# FPGA_board_V2.net
KiCad netlist of a schematic drawn in EAGLE
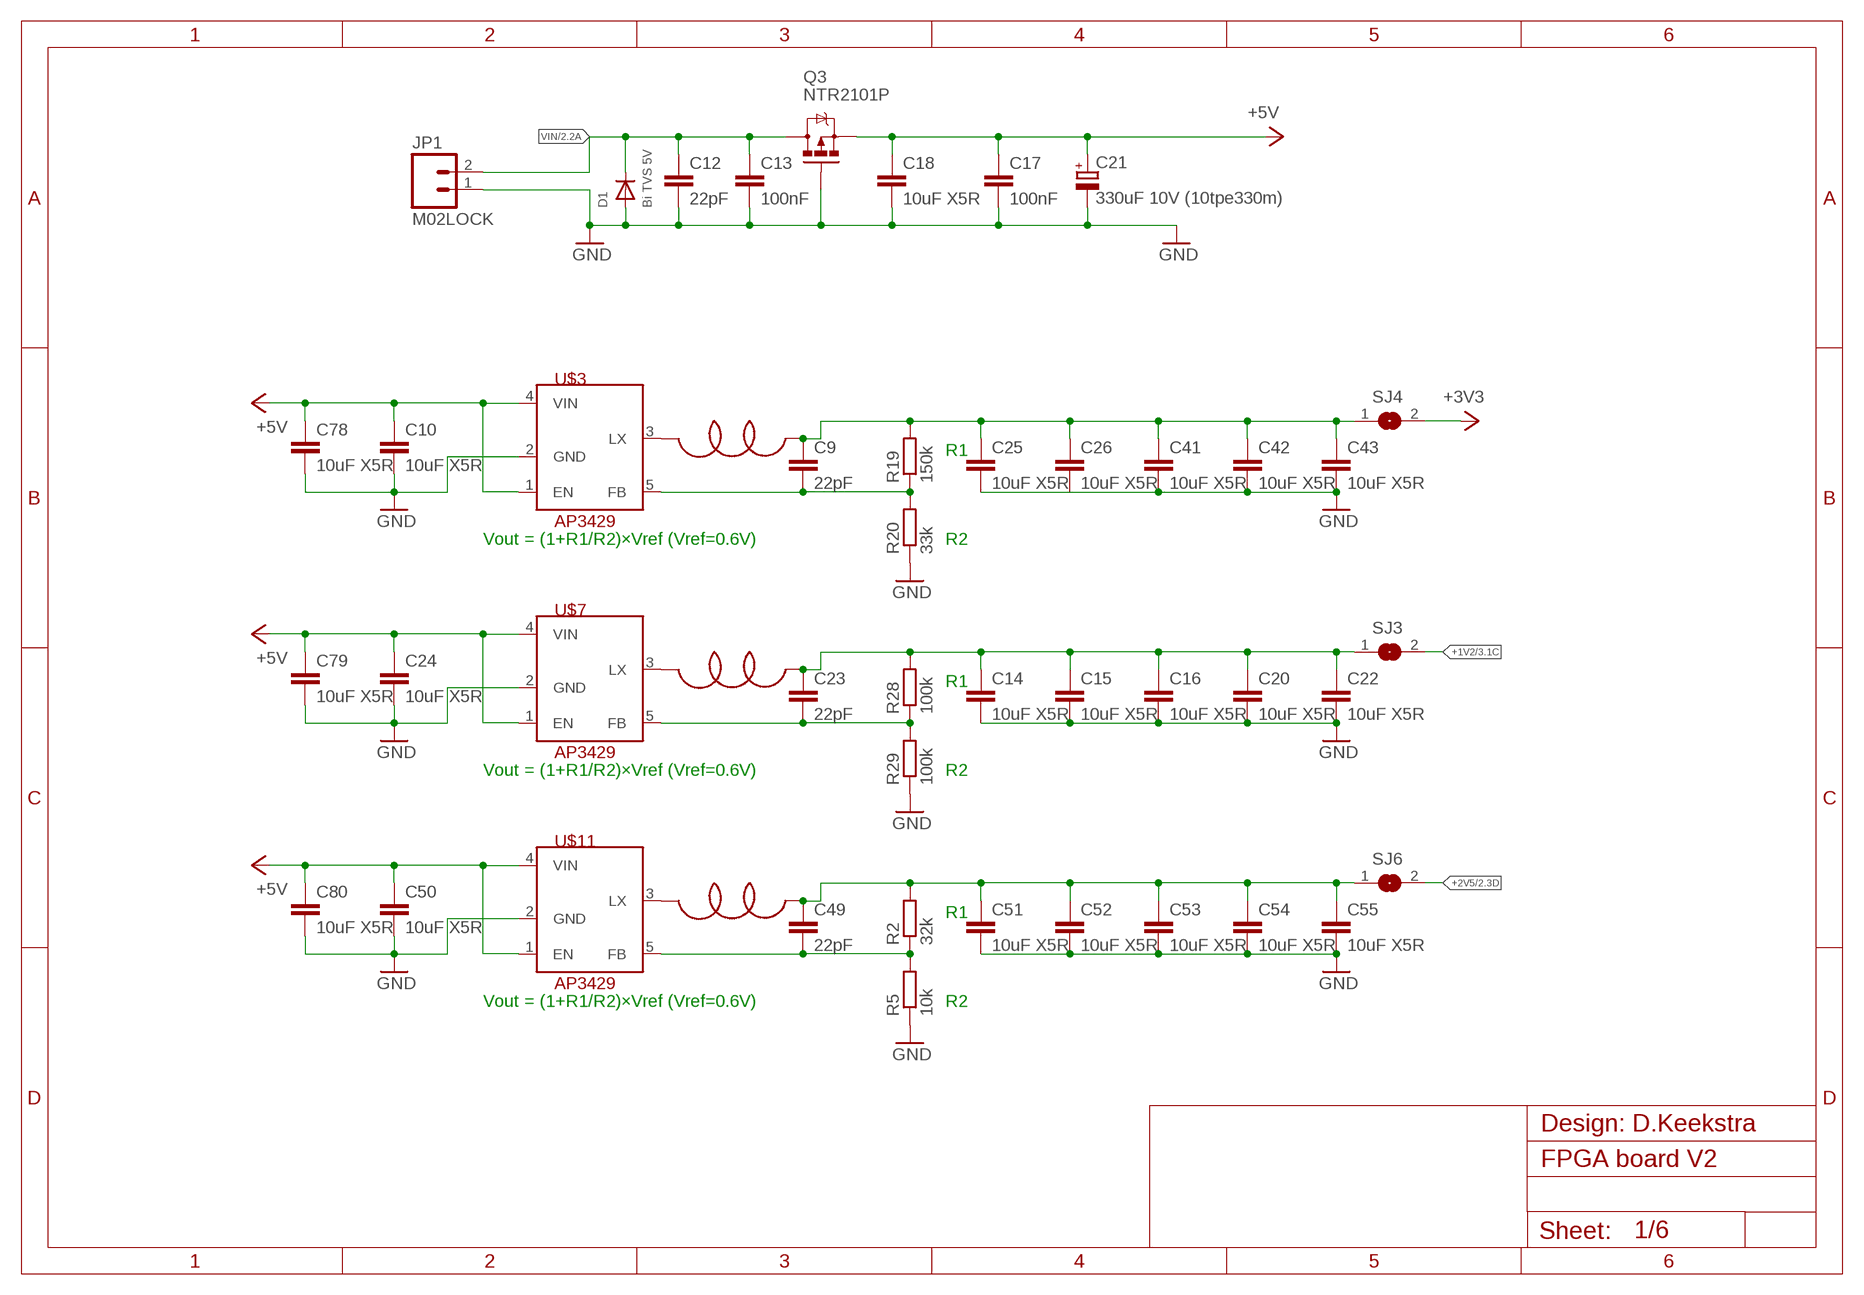
[diagram p0: schematic, sheet 1]
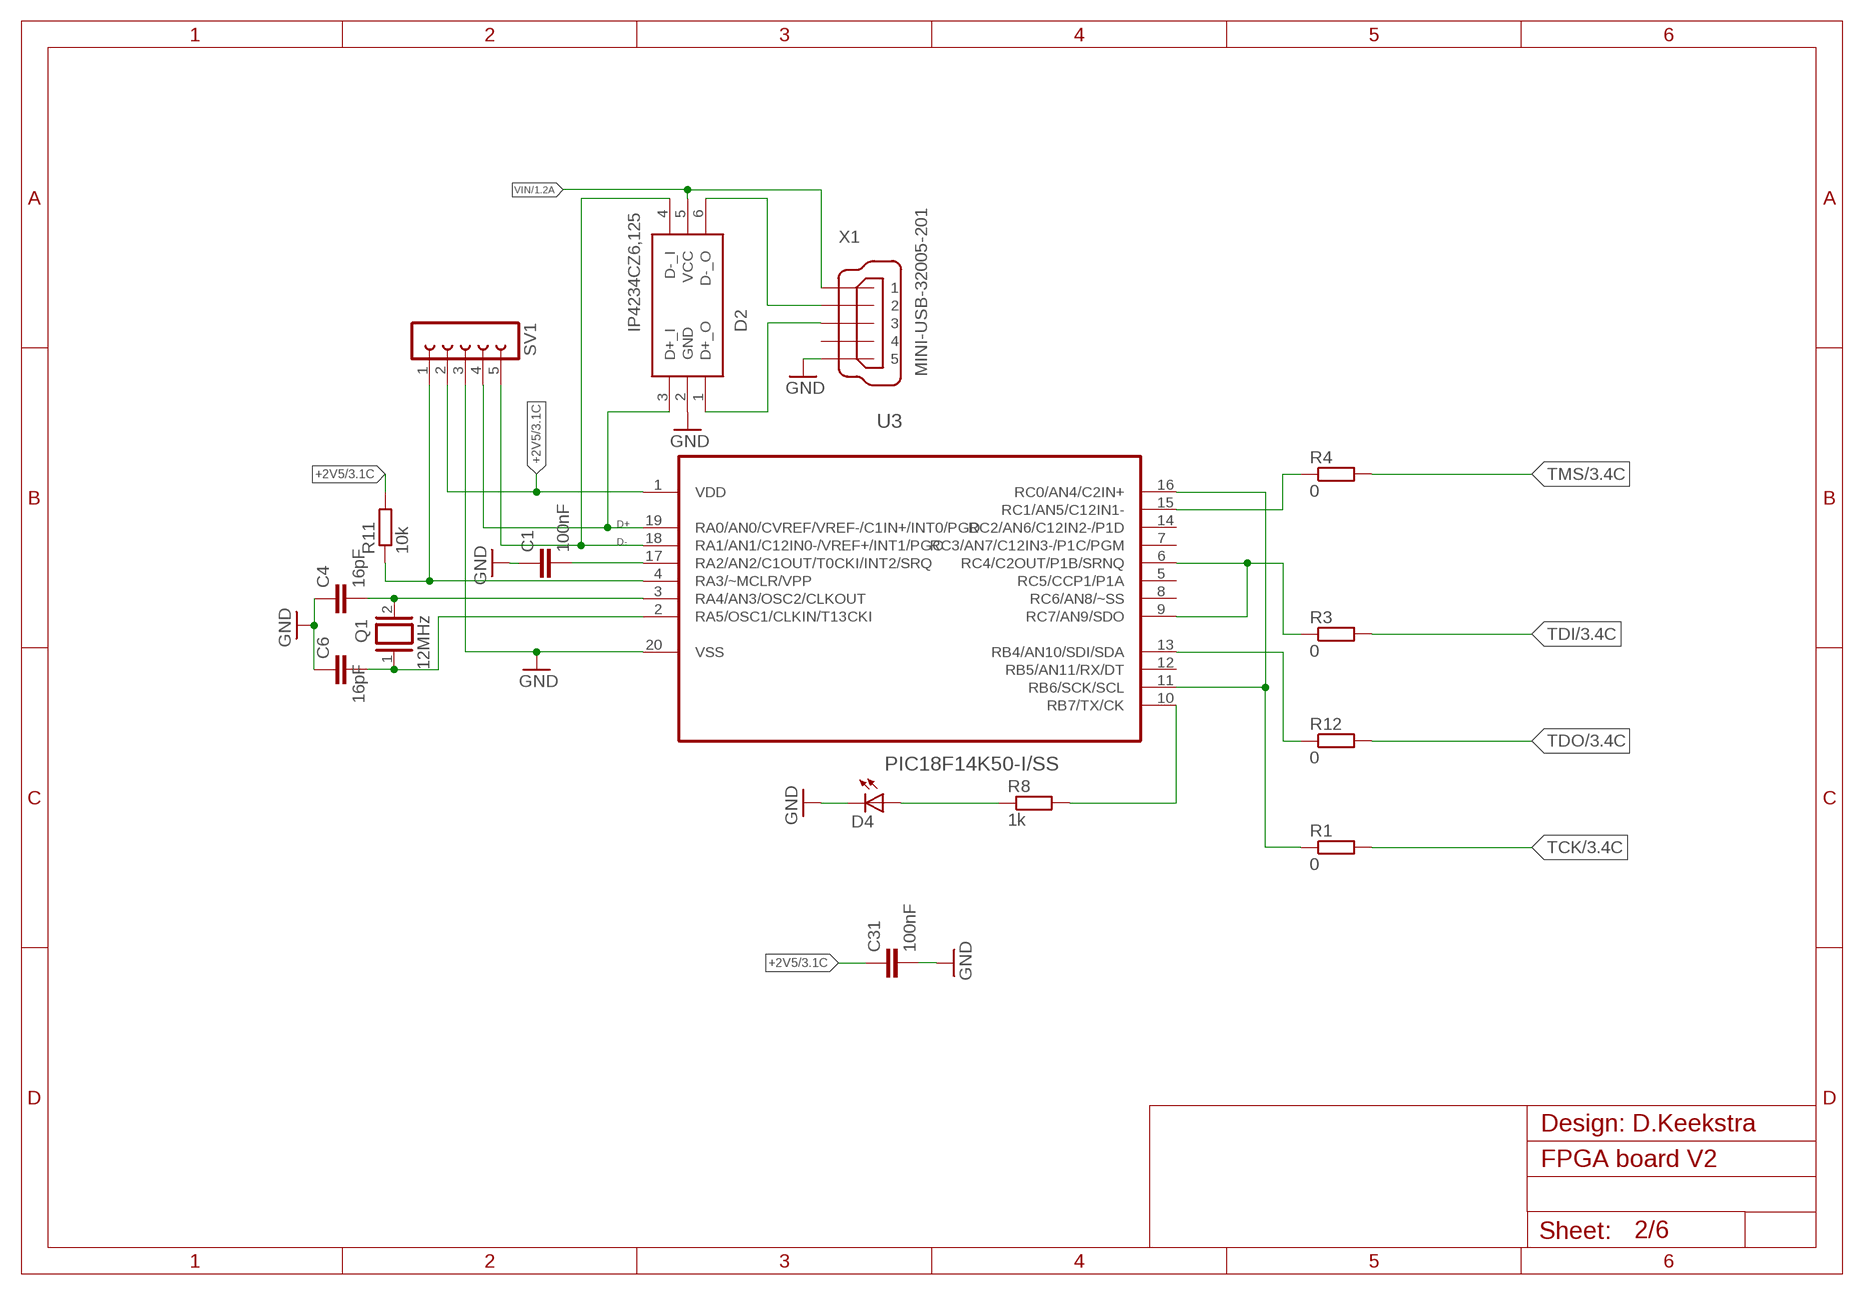
[diagram p1: schematic, sheet 2]
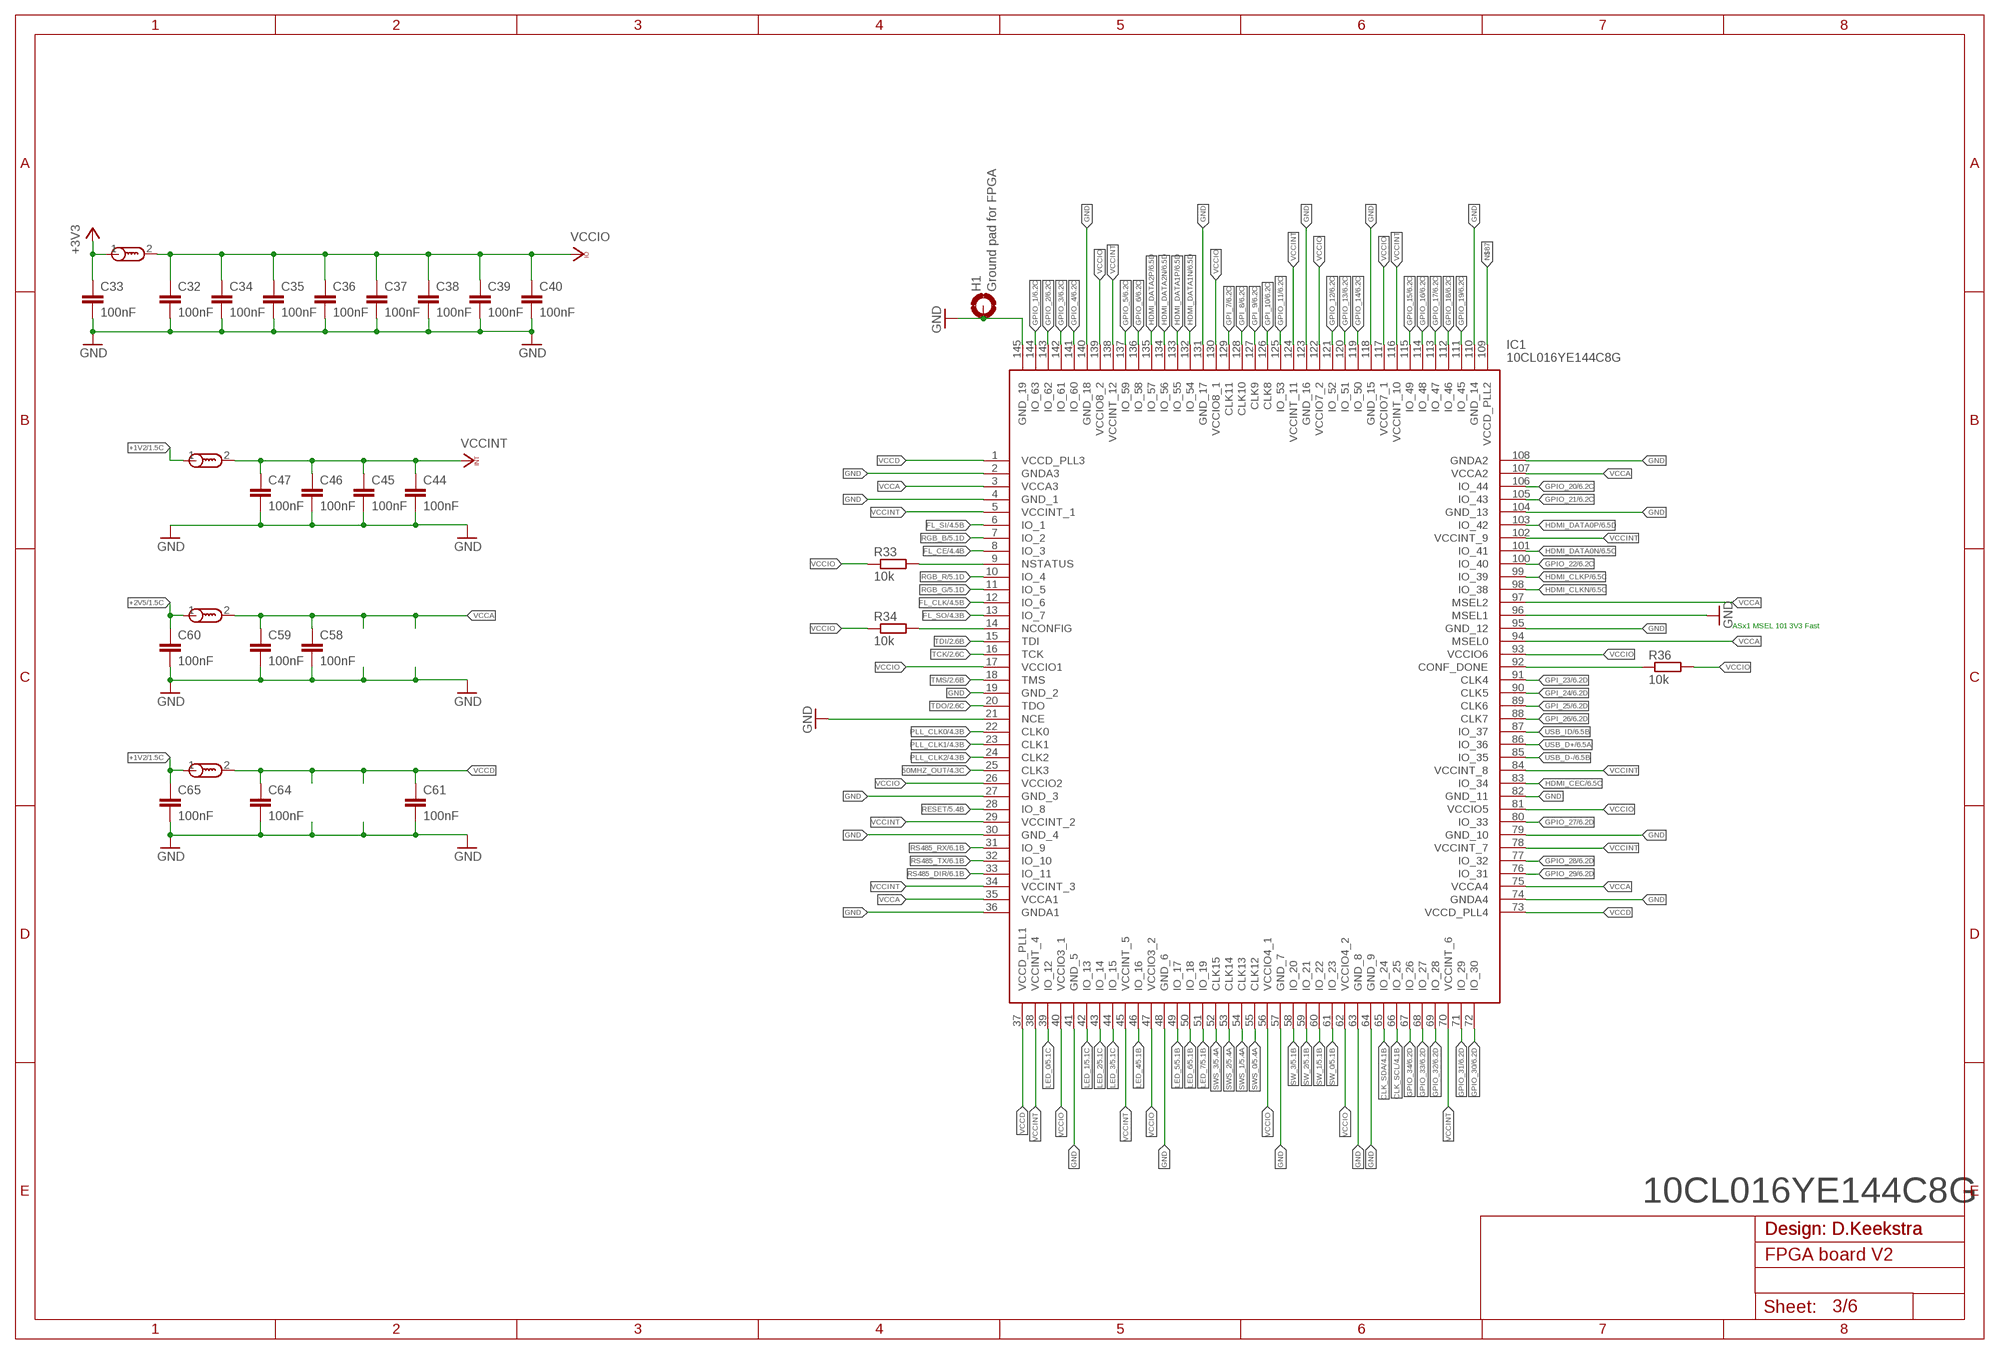
[diagram p2: schematic, sheet 3]
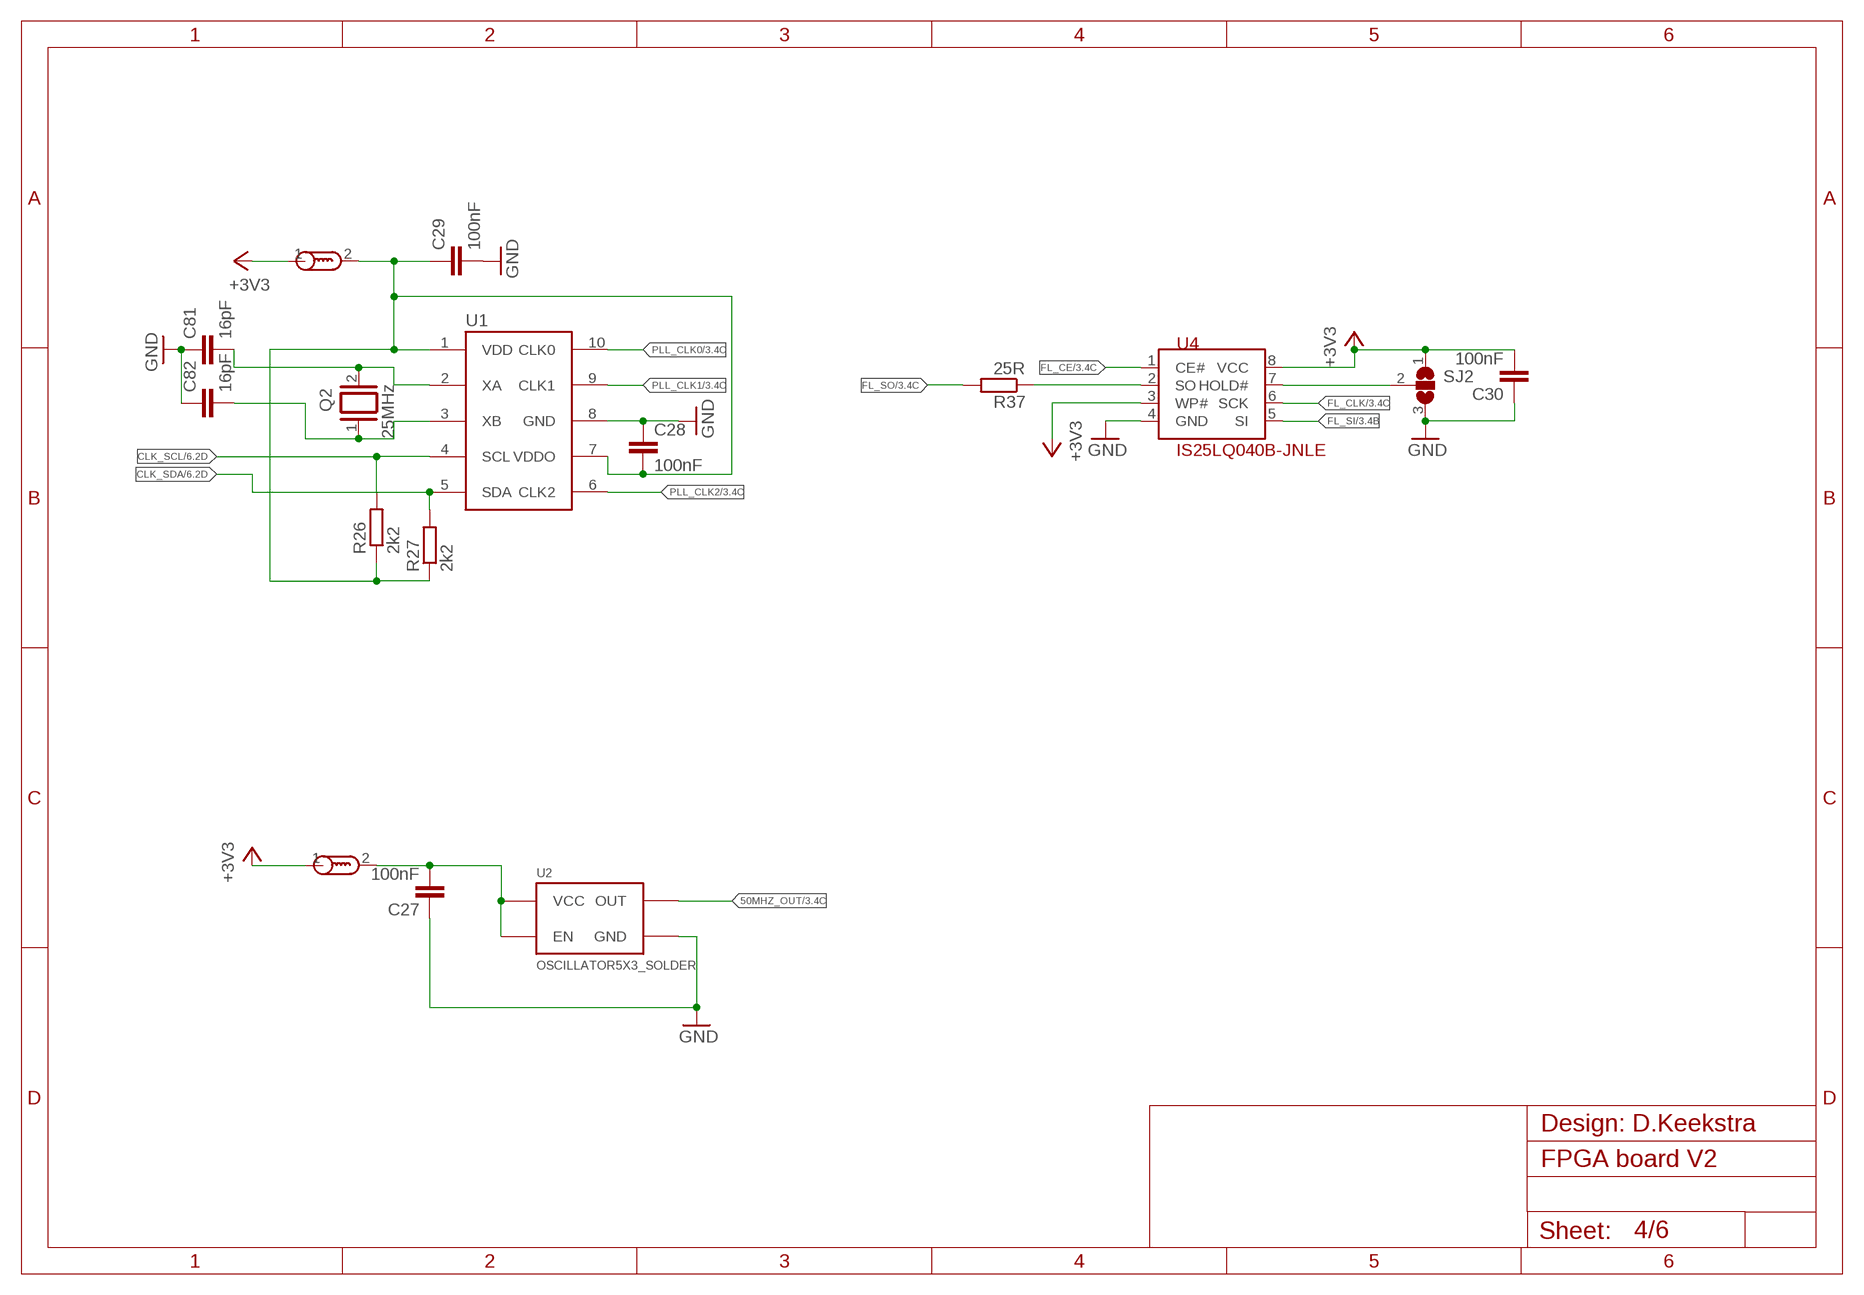
[diagram p3: schematic, sheet 4]
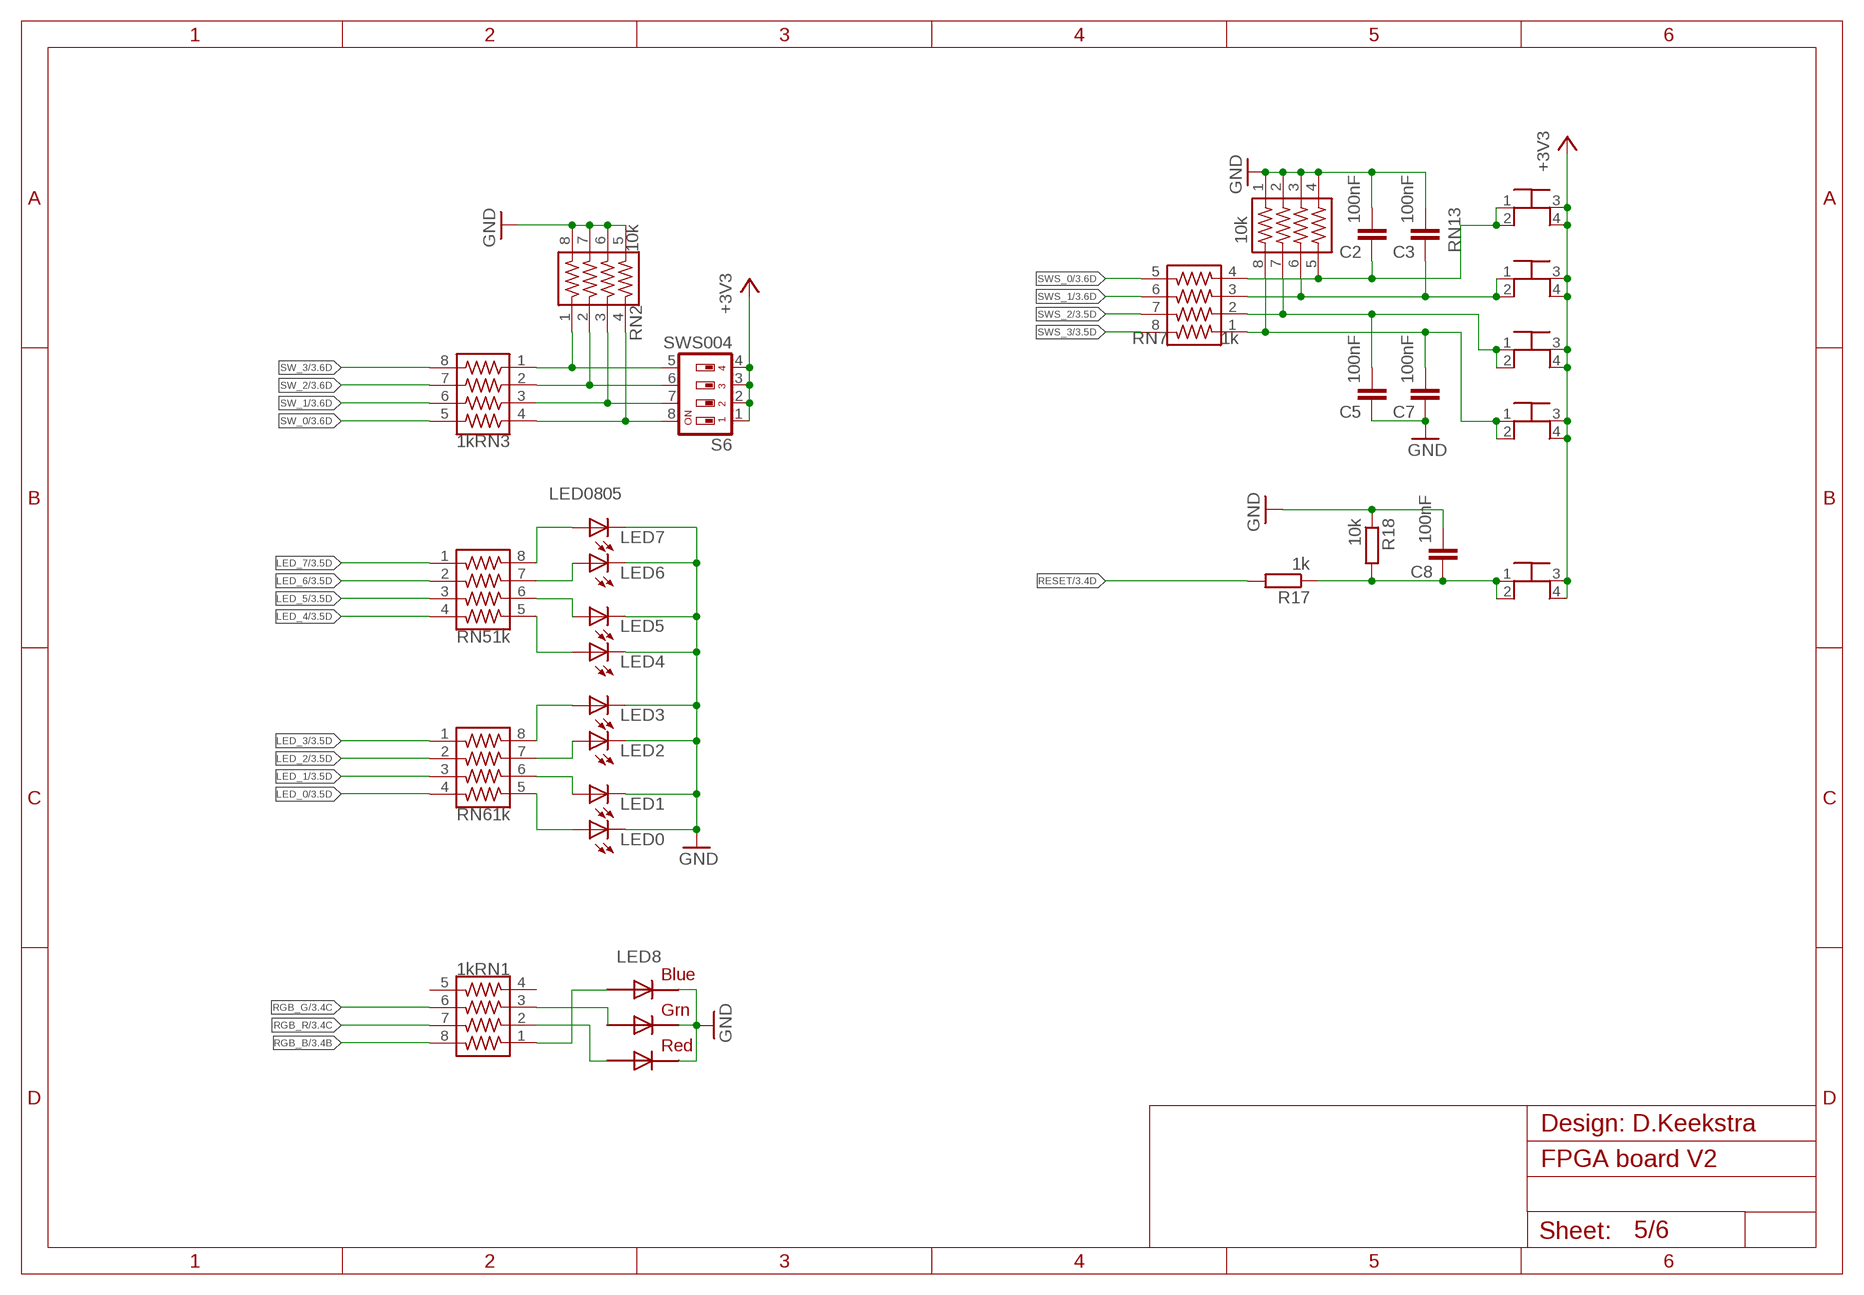
[diagram p4: schematic, sheet 5]
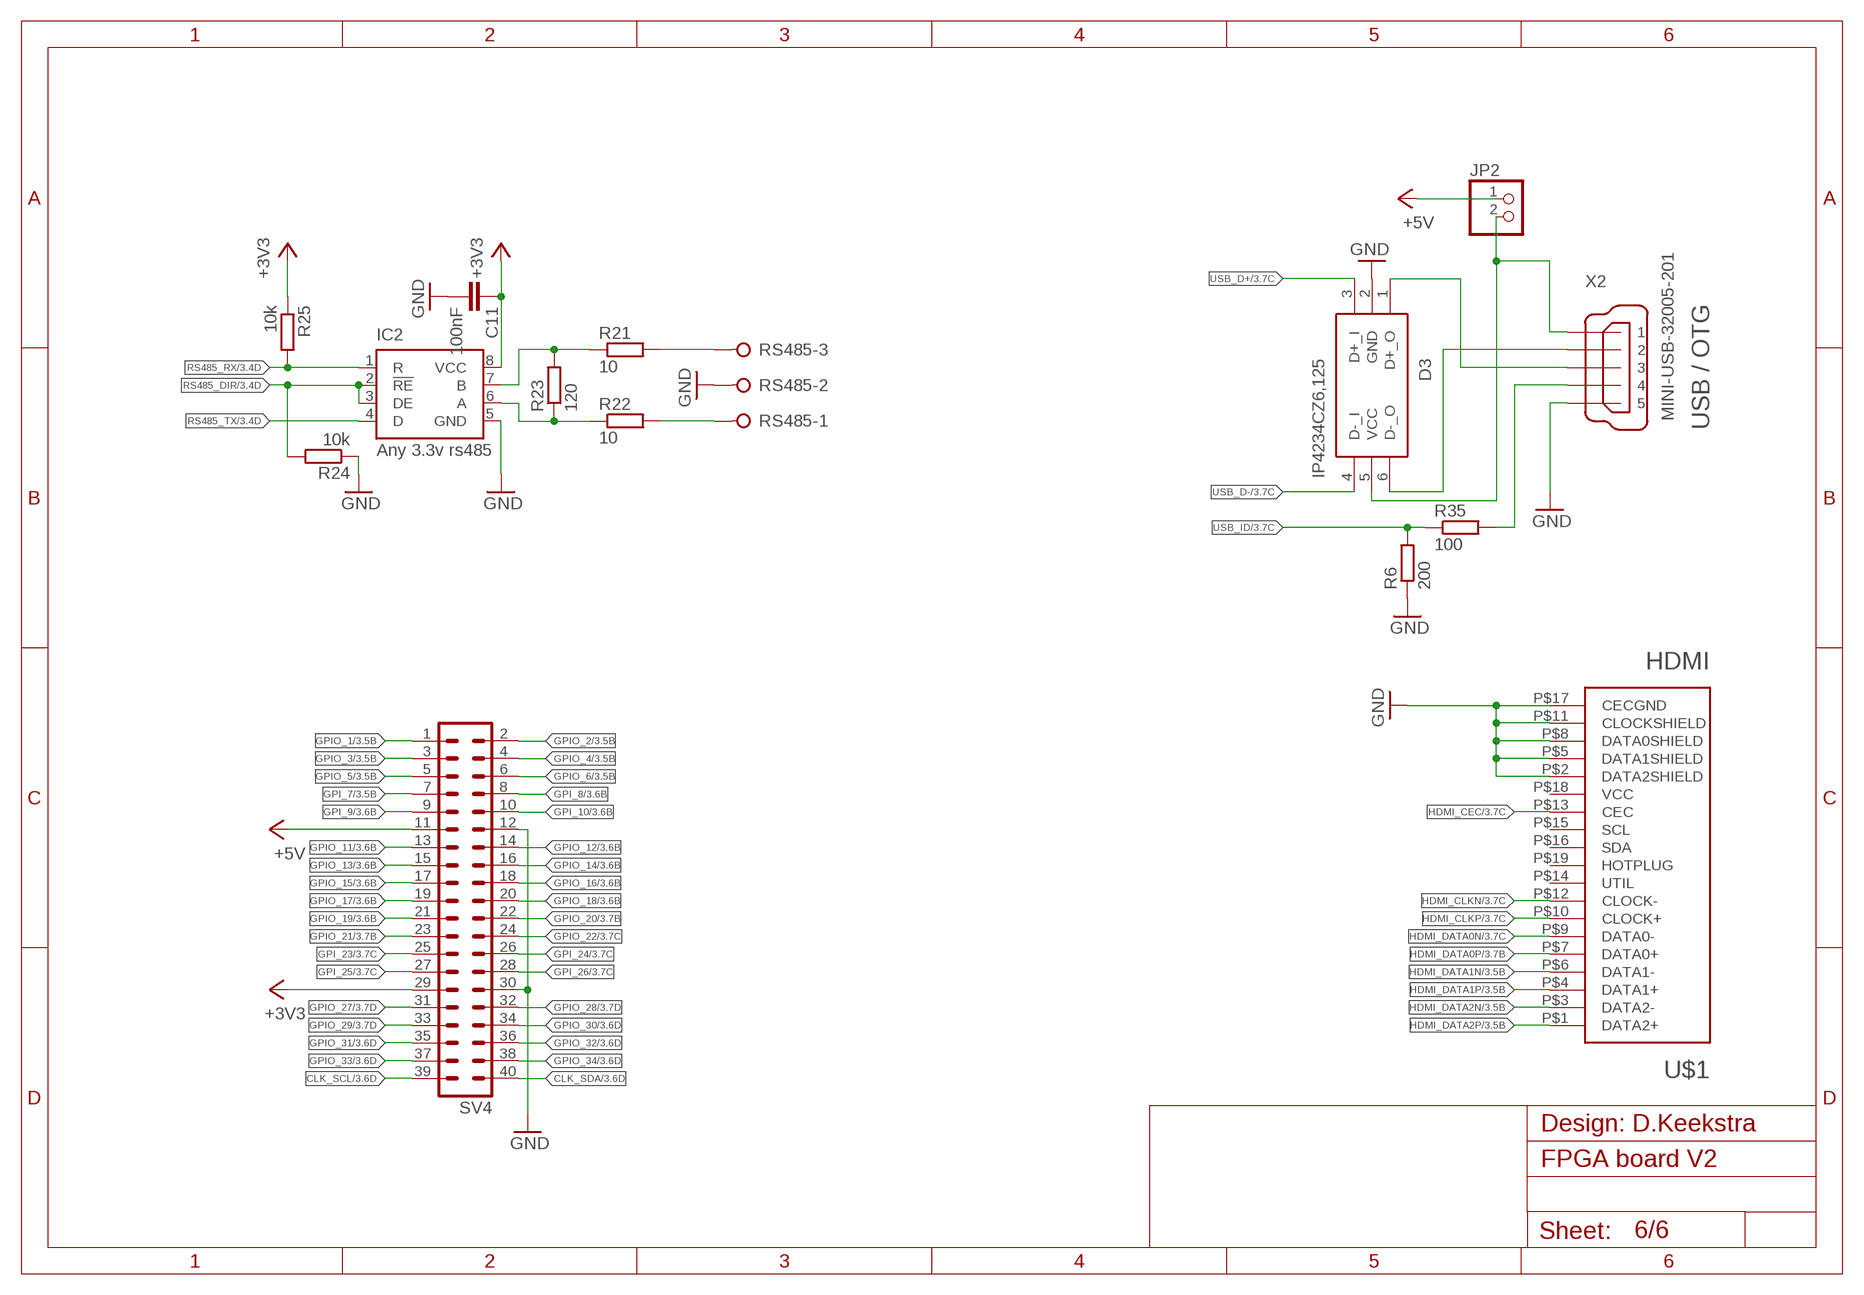
[diagram p5: schematic, sheet 6]

(export (version "E")
  (design (tool "Eeschema 10.0.6"))
  (components
    (comp (ref "C2")
      (value "100nF")
      (footprint "eagle-import:C0603")
      (libsource (lib "eagle-import") (part "C-EUC0603"))
    )
    (comp (ref "C3")
      (value "100nF")
      (footprint "eagle-import:C0603")
      (libsource (lib "eagle-import") (part "C-EUC0603"))
    )
    (comp (ref "C5")
      (value "100nF")
      (footprint "eagle-import:C0603")
      (libsource (lib "eagle-import") (part "C-EUC0603"))
    )
    (comp (ref "C7")
      (value "100nF")
      (footprint "eagle-import:C0603")
      (libsource (lib "eagle-import") (part "C-EUC0603"))
    )
    (comp (ref "C8")
      (value "100nF")
      (footprint "eagle-import:C0603")
      (libsource (lib "eagle-import") (part "C-EUC0603"))
    )
    (comp (ref "LED0")
      (value "LED0805")
      (footprint "eagle-import:CHIPLED_0805")
      (libsource (lib "eagle-import") (part "LED0805"))
    )
    (comp (ref "LED1")
      (value "LED0805")
      (footprint "eagle-import:CHIPLED_0805")
      (libsource (lib "eagle-import") (part "LED0805"))
    )
    (comp (ref "LED2")
      (value "LED0805")
      (footprint "eagle-import:CHIPLED_0805")
      (libsource (lib "eagle-import") (part "LED0805"))
    )
    (comp (ref "LED3")
      (value "LED0805")
      (footprint "eagle-import:CHIPLED_0805")
      (libsource (lib "eagle-import") (part "LED0805"))
    )
    (comp (ref "LED4")
      (value "LED0805")
      (footprint "eagle-import:CHIPLED_0805")
      (libsource (lib "eagle-import") (part "LED0805"))
    )
    (comp (ref "LED5")
      (value "LED0805")
      (footprint "eagle-import:CHIPLED_0805")
      (libsource (lib "eagle-import") (part "LED0805"))
    )
    (comp (ref "LED6")
      (value "LED0805")
      (footprint "eagle-import:CHIPLED_0805")
      (libsource (lib "eagle-import") (part "LED0805"))
    )
    (comp (ref "LED7")
      (value "LED0805")
      (footprint "eagle-import:CHIPLED_0805")
      (libsource (lib "eagle-import") (part "LED0805"))
    )
    (comp (ref "LED8")
      (value "RGBLED5050")
      (footprint "eagle-import:RGBLED5050")
      (libsource (lib "eagle-import") (part "RGBLED5050"))
    )
    (comp (ref "R17")
      (value "1k")
      (footprint "eagle-import:R0603")
      (libsource (lib "eagle-import") (part "R-EU_R0603"))
    )
    (comp (ref "R18")
      (value "10k")
      (footprint "eagle-import:R0603")
      (libsource (lib "eagle-import") (part "R-EU_R0603"))
    )
    (comp (ref "RN1")
      (value "1k")
      (footprint "eagle-import:744-8NS")
      (libsource (lib "eagle-import") (part "744-8NS"))
    )
    (comp (ref "RN2")
      (value "10k")
      (footprint "eagle-import:744-8NS")
      (libsource (lib "eagle-import") (part "744-8NS"))
    )
    (comp (ref "RN3")
      (value "1k")
      (footprint "eagle-import:744-8NS")
      (libsource (lib "eagle-import") (part "744-8NS"))
    )
    (comp (ref "RN5")
      (value "1k")
      (footprint "eagle-import:744-8NS")
      (libsource (lib "eagle-import") (part "744-8NS"))
    )
    (comp (ref "RN6")
      (value "1k")
      (footprint "eagle-import:744-8NS")
      (libsource (lib "eagle-import") (part "744-8NS"))
    )
    (comp (ref "RN7")
      (value "1k")
      (footprint "eagle-import:744-8NS")
      (libsource (lib "eagle-import") (part "744-8NS"))
    )
    (comp (ref "RN13")
      (value "10k")
      (footprint "eagle-import:744-8NS")
      (libsource (lib "eagle-import") (part "744-8NS"))
    )
    (comp (ref "S1")
      (value "SKQGADE010")
      (footprint "eagle-import:SKQGAKE010")
      (fields (field (name "MOUSER_PART_NUMBER") "688-SKQGAD"))
      (libsource (lib "eagle-import") (part "SKQGADE010"))
    )
    (comp (ref "S2")
      (value "SKQGADE010")
      (footprint "eagle-import:SKQGAKE010")
      (fields (field (name "MOUSER_PART_NUMBER") "688-SKQGAD"))
      (libsource (lib "eagle-import") (part "SKQGADE010"))
    )
    (comp (ref "S3")
      (value "SKQGADE010")
      (footprint "eagle-import:SKQGAKE010")
      (fields (field (name "MOUSER_PART_NUMBER") "688-SKQGAD"))
      (libsource (lib "eagle-import") (part "SKQGADE010"))
    )
    (comp (ref "S4")
      (value "SKQGADE010")
      (footprint "eagle-import:SKQGAKE010")
      (fields (field (name "MOUSER_PART_NUMBER") "688-SKQGAD"))
      (libsource (lib "eagle-import") (part "SKQGADE010"))
    )
    (comp (ref "S5")
      (value "SKQGADE010")
      (footprint "eagle-import:SKQGAKE010")
      (fields (field (name "MOUSER_PART_NUMBER") "688-SKQGAD"))
      (libsource (lib "eagle-import") (part "SKQGADE010"))
    )
    (comp (ref "S6")
      (value "SWS004")
      (footprint "eagle-import:SMS-004")
      (libsource (lib "eagle-import") (part "SWS004"))
    )
    (comp (ref "C9")
      (value "22pF")
      (footprint "eagle-import:C0603")
      (libsource (lib "eagle-import") (part "C-EUC0603"))
    )
    (comp (ref "C10")
      (value "10uF X5R")
      (footprint "eagle-import:C0805K")
      (libsource (lib "eagle-import") (part "C-EUC0805K"))
    )
    (comp (ref "C12")
      (value "22pF")
      (footprint "eagle-import:C0603")
      (libsource (lib "eagle-import") (part "C-EUC0603"))
    )
    (comp (ref "C13")
      (value "100nF")
      (footprint "eagle-import:C0603")
      (libsource (lib "eagle-import") (part "C-EUC0603"))
    )
    (comp (ref "C14")
      (value "10uF X5R")
      (footprint "eagle-import:C0805K")
      (libsource (lib "eagle-import") (part "C-EUC0805K"))
    )
    (comp (ref "C15")
      (value "10uF X5R")
      (footprint "eagle-import:C0805K")
      (libsource (lib "eagle-import") (part "C-EUC0805K"))
    )
    (comp (ref "C16")
      (value "10uF X5R")
      (footprint "eagle-import:C0805K")
      (libsource (lib "eagle-import") (part "C-EUC0805K"))
    )
    (comp (ref "C17")
      (value "100nF")
      (footprint "eagle-import:C0603")
      (libsource (lib "eagle-import") (part "C-EUC0603"))
    )
    (comp (ref "C18")
      (value "10uF X5R")
      (footprint "eagle-import:C0805K")
      (libsource (lib "eagle-import") (part "C-EUC0805K"))
    )
    (comp (ref "C20")
      (value "10uF X5R")
      (footprint "eagle-import:C0805K")
      (libsource (lib "eagle-import") (part "C-EUC0805K"))
    )
    (comp (ref "C21")
      (value "330uF 10V (10tpe330m)")
      (footprint "eagle-import:D_7343-31W")
      (libsource (lib "eagle-import") (part "CPOL-EUD/7343-31W"))
    )
    (comp (ref "C22")
      (value "10uF X5R")
      (footprint "eagle-import:C0805K")
      (libsource (lib "eagle-import") (part "C-EUC0805K"))
    )
    (comp (ref "C23")
      (value "22pF")
      (footprint "eagle-import:C0603")
      (libsource (lib "eagle-import") (part "C-EUC0603"))
    )
    (comp (ref "C24")
      (value "10uF X5R")
      (footprint "eagle-import:C0805K")
      (libsource (lib "eagle-import") (part "C-EUC0805K"))
    )
    (comp (ref "C25")
      (value "10uF X5R")
      (footprint "eagle-import:C0805K")
      (libsource (lib "eagle-import") (part "C-EUC0805K"))
    )
    (comp (ref "C26")
      (value "10uF X5R")
      (footprint "eagle-import:C0805K")
      (libsource (lib "eagle-import") (part "C-EUC0805K"))
    )
    (comp (ref "C41")
      (value "10uF X5R")
      (footprint "eagle-import:C0805K")
      (libsource (lib "eagle-import") (part "C-EUC0805K"))
    )
    (comp (ref "C42")
      (value "10uF X5R")
      (footprint "eagle-import:C0805K")
      (libsource (lib "eagle-import") (part "C-EUC0805K"))
    )
    (comp (ref "C43")
      (value "10uF X5R")
      (footprint "eagle-import:C0805K")
      (libsource (lib "eagle-import") (part "C-EUC0805K"))
    )
    (comp (ref "C49")
      (value "22pF")
      (footprint "eagle-import:C0603")
      (libsource (lib "eagle-import") (part "C-EUC0603"))
    )
    (comp (ref "C50")
      (value "10uF X5R")
      (footprint "eagle-import:C0805K")
      (libsource (lib "eagle-import") (part "C-EUC0805K"))
    )
    (comp (ref "C51")
      (value "10uF X5R")
      (footprint "eagle-import:C0805K")
      (libsource (lib "eagle-import") (part "C-EUC0805K"))
    )
    (comp (ref "C52")
      (value "10uF X5R")
      (footprint "eagle-import:C0805K")
      (libsource (lib "eagle-import") (part "C-EUC0805K"))
    )
    (comp (ref "C53")
      (value "10uF X5R")
      (footprint "eagle-import:C0805K")
      (libsource (lib "eagle-import") (part "C-EUC0805K"))
    )
    (comp (ref "C54")
      (value "10uF X5R")
      (footprint "eagle-import:C0805K")
      (libsource (lib "eagle-import") (part "C-EUC0805K"))
    )
    (comp (ref "C55")
      (value "10uF X5R")
      (footprint "eagle-import:C0805K")
      (libsource (lib "eagle-import") (part "C-EUC0805K"))
    )
    (comp (ref "C78")
      (value "10uF X5R")
      (footprint "eagle-import:C0805K")
      (libsource (lib "eagle-import") (part "C-EUC0805K"))
    )
    (comp (ref "C79")
      (value "10uF X5R")
      (footprint "eagle-import:C0805K")
      (libsource (lib "eagle-import") (part "C-EUC0805K"))
    )
    (comp (ref "C80")
      (value "10uF X5R")
      (footprint "eagle-import:C0805K")
      (libsource (lib "eagle-import") (part "C-EUC0805K"))
    )
    (comp (ref "D1")
      (value "Bi TVS 5V")
      (footprint "eagle-import:SOD-523")
      (libsource (lib "eagle-import") (part "DIODESOD-523"))
    )
    (comp (ref "JP1")
      (value "M02LOCK")
      (footprint "eagle-import:1X02_LOCK")
      (libsource (lib "eagle-import") (part "M02LOCK"))
    )
    (comp (ref "L2")
      (value "3.3uH 1.9A PWR")
      (footprint "eagle-import:SLF7032T")
      (libsource (lib "eagle-import") (part "SLF7032T3R3M1R9-2-PF"))
    )
    (comp (ref "L3")
      (value "3.3uH 1.9A PWR")
      (footprint "eagle-import:SLF7032T")
      (libsource (lib "eagle-import") (part "SLF7032T3R3M1R9-2-PF"))
    )
    (comp (ref "L4")
      (value "3.3uH 1.9A PWR")
      (footprint "eagle-import:SLF7032T")
      (libsource (lib "eagle-import") (part "SLF7032T3R3M1R9-2-PF"))
    )
    (comp (ref "Q3")
      (value "NTR2101P")
      (footprint "eagle-import:SOT23-3")
      (libsource (lib "eagle-import") (part "MOSFET-PCHANNELIRLML2244"))
    )
    (comp (ref "R2")
      (value "32k")
      (footprint "eagle-import:R0603")
      (libsource (lib "eagle-import") (part "R-EU_R0603"))
    )
    (comp (ref "R5")
      (value "10k")
      (footprint "eagle-import:R0603")
      (libsource (lib "eagle-import") (part "R-EU_R0603"))
    )
    (comp (ref "R19")
      (value "150k")
      (footprint "eagle-import:R0603")
      (libsource (lib "eagle-import") (part "R-EU_R0603"))
    )
    (comp (ref "R20")
      (value "33k")
      (footprint "eagle-import:R0603")
      (libsource (lib "eagle-import") (part "R-EU_R0603"))
    )
    (comp (ref "R28")
      (value "100k")
      (footprint "eagle-import:R0603")
      (libsource (lib "eagle-import") (part "R-EU_R0603"))
    )
    (comp (ref "R29")
      (value "100k")
      (footprint "eagle-import:R0603")
      (libsource (lib "eagle-import") (part "R-EU_R0603"))
    )
    (comp (ref "SJ3") (value "SJ") (footprint "eagle-import:SJ") (libsource (lib "eagle-import") (part "SJ")))
    (comp (ref "SJ4") (value "SJ") (footprint "eagle-import:SJ") (libsource (lib "eagle-import") (part "SJ")))
    (comp (ref "SJ6") (value "SJ") (footprint "eagle-import:SJ") (libsource (lib "eagle-import") (part "SJ")))
    (comp (ref "U$3")
      (value "AP3429")
      (footprint "eagle-import:TSOT-25")
      (libsource (lib "eagle-import") (part "AP3429"))
    )
    (comp (ref "U$7")
      (value "AP3429")
      (footprint "eagle-import:TSOT-25")
      (libsource (lib "eagle-import") (part "AP3429"))
    )
    (comp (ref "U$11")
      (value "AP3429")
      (footprint "eagle-import:TSOT-25")
      (libsource (lib "eagle-import") (part "AP3429"))
    )
    (comp (ref "B5")
      (value "B-EU")
      (footprint "eagle-import:C0603")
      (libsource (lib "eagle-import") (part "B-EU"))
    )
    (comp (ref "B6")
      (value "B-EU")
      (footprint "eagle-import:C0603")
      (libsource (lib "eagle-import") (part "B-EU"))
    )
    (comp (ref "C27")
      (value "100nF")
      (footprint "eagle-import:C0603")
      (libsource (lib "eagle-import") (part "C-EUC0603"))
    )
    (comp (ref "C28")
      (value "100nF")
      (footprint "eagle-import:C0603")
      (libsource (lib "eagle-import") (part "C-EUC0603"))
    )
    (comp (ref "C29")
      (value "100nF")
      (footprint "eagle-import:C0603")
      (libsource (lib "eagle-import") (part "C-EUC0603"))
    )
    (comp (ref "C30")
      (value "100nF")
      (footprint "eagle-import:C0603")
      (libsource (lib "eagle-import") (part "C-EUC0603"))
    )
    (comp (ref "C81")
      (value "16pF")
      (footprint "eagle-import:C0603")
      (libsource (lib "eagle-import") (part "C-EUC0603"))
    )
    (comp (ref "C82")
      (value "16pF")
      (footprint "eagle-import:C0603")
      (libsource (lib "eagle-import") (part "C-EUC0603"))
    )
    (comp (ref "Q2")
      (value "25MHz")
      (footprint "eagle-import:QS")
      (libsource (lib "eagle-import") (part "XTAL/S"))
    )
    (comp (ref "R26")
      (value "2k2")
      (footprint "eagle-import:R0603")
      (libsource (lib "eagle-import") (part "resistor_R-EU_R0603"))
    )
    (comp (ref "R27")
      (value "2k2")
      (footprint "eagle-import:R0603")
      (libsource (lib "eagle-import") (part "resistor_R-EU_R0603"))
    )
    (comp (ref "R37")
      (value "25R")
      (footprint "eagle-import:R0603")
      (libsource (lib "eagle-import") (part "resistor_R-EU_R0603"))
    )
    (comp (ref "SJ2")
      (value "SJ2W")
      (footprint "eagle-import:SJ_2")
      (libsource (lib "eagle-import") (part "SJ2W"))
    )
    (comp (ref "U1")
      (value "SI5351A_CLOCK_GEN")
      (footprint "eagle-import:MSOP-10")
      (libsource (lib "eagle-import") (part "SI5351A_CLOCK_GEN"))
    )
    (comp (ref "U2")
      (value "OSCILLATOR5X3_SOLDER")
      (footprint "eagle-import:CRYSTAL-SMD-5X3_SOLDER")
      (libsource (lib "eagle-import") (part "OSCILLATOR5X3_SOLDER"))
    )
    (comp (ref "U4")
      (value "IS25LQ040B-JNLE")
      (footprint "eagle-import:SOIC8")
      (libsource (lib "eagle-import") (part "IS25LQ040B-JNLE"))
    )
    (comp (ref "B1")
      (value "B-EU")
      (footprint "eagle-import:C0603")
      (libsource (lib "eagle-import") (part "B-EU"))
    )
    (comp (ref "B2")
      (value "B-EU")
      (footprint "eagle-import:C0603")
      (libsource (lib "eagle-import") (part "B-EU"))
    )
    (comp (ref "B3")
      (value "B-EU")
      (footprint "eagle-import:C0603")
      (libsource (lib "eagle-import") (part "B-EU"))
    )
    (comp (ref "B4")
      (value "B-EU")
      (footprint "eagle-import:C0603")
      (libsource (lib "eagle-import") (part "B-EU"))
    )
    (comp (ref "C32")
      (value "100nF")
      (footprint "eagle-import:C0603")
      (libsource (lib "eagle-import") (part "C-EUC0603"))
    )
    (comp (ref "C33")
      (value "100nF")
      (footprint "eagle-import:C0603")
      (libsource (lib "eagle-import") (part "C-EUC0603"))
    )
    (comp (ref "C34")
      (value "100nF")
      (footprint "eagle-import:C0603")
      (libsource (lib "eagle-import") (part "C-EUC0603"))
    )
    (comp (ref "C35")
      (value "100nF")
      (footprint "eagle-import:C0603")
      (libsource (lib "eagle-import") (part "C-EUC0603"))
    )
    (comp (ref "C36")
      (value "100nF")
      (footprint "eagle-import:C0603")
      (libsource (lib "eagle-import") (part "C-EUC0603"))
    )
    (comp (ref "C37")
      (value "100nF")
      (footprint "eagle-import:C0603")
      (libsource (lib "eagle-import") (part "C-EUC0603"))
    )
    (comp (ref "C38")
      (value "100nF")
      (footprint "eagle-import:C0603")
      (libsource (lib "eagle-import") (part "C-EUC0603"))
    )
    (comp (ref "C39")
      (value "100nF")
      (footprint "eagle-import:C0603")
      (libsource (lib "eagle-import") (part "C-EUC0603"))
    )
    (comp (ref "C40")
      (value "100nF")
      (footprint "eagle-import:C0603")
      (libsource (lib "eagle-import") (part "C-EUC0603"))
    )
    (comp (ref "C44")
      (value "100nF")
      (footprint "eagle-import:C0603")
      (libsource (lib "eagle-import") (part "C-EUC0603"))
    )
    (comp (ref "C45")
      (value "100nF")
      (footprint "eagle-import:C0603")
      (libsource (lib "eagle-import") (part "C-EUC0603"))
    )
    (comp (ref "C46")
      (value "100nF")
      (footprint "eagle-import:C0603")
      (libsource (lib "eagle-import") (part "C-EUC0603"))
    )
    (comp (ref "C47")
      (value "100nF")
      (footprint "eagle-import:C0603")
      (libsource (lib "eagle-import") (part "C-EUC0603"))
    )
    (comp (ref "C58")
      (value "100nF")
      (footprint "eagle-import:C0603")
      (libsource (lib "eagle-import") (part "C-EUC0603"))
    )
    (comp (ref "C59")
      (value "100nF")
      (footprint "eagle-import:C0603")
      (libsource (lib "eagle-import") (part "C-EUC0603"))
    )
    (comp (ref "C60")
      (value "100nF")
      (footprint "eagle-import:C0603")
      (libsource (lib "eagle-import") (part "C-EUC0603"))
    )
    (comp (ref "C61")
      (value "100nF")
      (footprint "eagle-import:C0603")
      (libsource (lib "eagle-import") (part "C-EUC0603"))
    )
    (comp (ref "C64")
      (value "100nF")
      (footprint "eagle-import:C0603")
      (libsource (lib "eagle-import") (part "C-EUC0603"))
    )
    (comp (ref "C65")
      (value "100nF")
      (footprint "eagle-import:C0603")
      (libsource (lib "eagle-import") (part "C-EUC0603"))
    )
    (comp (ref "H1")
      (value "Ground pad for FPGA")
      (footprint "eagle-import:2,8-PAD")
      (libsource (lib "eagle-import") (part "MOUNT-PAD-ROUND2.8"))
    )
    (comp (ref "IC1")
      (value "10CL016YE144C8G")
      (footprint "eagle-import:QFP50P2200X2200X165-145N")
      (fields (field (name "MOUSER_PART_NUMBER") "989-10CL016YE144C8G"))
      (libsource (lib "eagle-import") (part "10CL016YE144C8G"))
    )
    (comp (ref "R33")
      (value "10k")
      (footprint "eagle-import:R0603")
      (libsource (lib "eagle-import") (part "R-EU_R0603"))
    )
    (comp (ref "R34")
      (value "10k")
      (footprint "eagle-import:R0603")
      (libsource (lib "eagle-import") (part "R-EU_R0603"))
    )
    (comp (ref "R36")
      (value "10k")
      (footprint "eagle-import:R0603")
      (libsource (lib "eagle-import") (part "R-EU_R0603"))
    )
    (comp (ref "C11")
      (value "100nF")
      (footprint "eagle-import:C0603")
      (libsource (lib "eagle-import") (part "C-EUC0603"))
    )
    (comp (ref "D3")
      (value "IP4234CZ6,125")
      (footprint "eagle-import:SOT95P275X110-6N")
      (fields (field (name "MOUSER_PART_NUMBER") "771-IP4234CZ6125"))
      (libsource (lib "eagle-import") (part "IP4234CZ6,125"))
    )
    (comp (ref "IC2")
      (value "Any 3.3v rs485")
      (footprint "eagle-import:SO-08")
      (fields (field (name "MF") "TEXAS INSTRUMENTS") (field (name "MPN") "SN65176BD"))
      (libsource (lib "eagle-import") (part "SN65176D"))
    )
    (comp (ref "JP2")
      (value "PINHD-1X2")
      (footprint "eagle-import:1X02")
      (libsource (lib "eagle-import") (part "PINHD-1X2"))
    )
    (comp (ref "R6")
      (value "200")
      (footprint "eagle-import:R0603")
      (libsource (lib "eagle-import") (part "resistor_R-EU_R0603"))
    )
    (comp (ref "R21")
      (value "10")
      (footprint "eagle-import:R0603")
      (libsource (lib "eagle-import") (part "resistor_R-EU_R0603"))
    )
    (comp (ref "R22")
      (value "10")
      (footprint "eagle-import:R0603")
      (libsource (lib "eagle-import") (part "resistor_R-EU_R0603"))
    )
    (comp (ref "R23")
      (value "120")
      (footprint "eagle-import:R0603")
      (libsource (lib "eagle-import") (part "resistor_R-EU_R0603"))
    )
    (comp (ref "R24")
      (value "10k")
      (footprint "eagle-import:R0603")
      (libsource (lib "eagle-import") (part "resistor_R-EU_R0603"))
    )
    (comp (ref "R25")
      (value "10k")
      (footprint "eagle-import:R0603")
      (libsource (lib "eagle-import") (part "resistor_R-EU_R0603"))
    )
    (comp (ref "R35")
      (value "100")
      (footprint "eagle-import:R0603")
      (libsource (lib "eagle-import") (part "resistor_R-EU_R0603"))
    )
    (comp (ref "RS485")
      (value "W237-3E")
      (footprint "eagle-import:W237-3E")
      (libsource (lib "eagle-import") (part "W237-3E"))
    )
    (comp (ref "SV4")
      (value "MA20-2")
      (footprint "eagle-import:MA20-2")
      (libsource (lib "eagle-import") (part "MA20-2"))
    )
    (comp (ref "U$1")
      (value "HDMI")
      (footprint "eagle-import:HDMI_A")
      (libsource (lib "eagle-import") (part "HDMI"))
    )
    (comp (ref "X2")
      (value "MINI-USB-32005-201")
      (footprint "eagle-import:32005-201")
      (libsource (lib "eagle-import") (part "MINI-USB-32005-201"))
    )
    (comp (ref "C1")
      (value "100nF")
      (footprint "eagle-import:C0603")
      (libsource (lib "eagle-import") (part "C-EUC0603"))
    )
    (comp (ref "C4")
      (value "16pF")
      (footprint "eagle-import:C0603")
      (libsource (lib "eagle-import") (part "C-EUC0603"))
    )
    (comp (ref "C6")
      (value "16pF")
      (footprint "eagle-import:C0603")
      (libsource (lib "eagle-import") (part "C-EUC0603"))
    )
    (comp (ref "C31")
      (value "100nF")
      (footprint "eagle-import:C0603")
      (libsource (lib "eagle-import") (part "C-EUC0603"))
    )
    (comp (ref "D2")
      (value "IP4234CZ6,125")
      (footprint "eagle-import:SOT95P275X110-6N")
      (fields (field (name "MOUSER_PART_NUMBER") "771-IP4234CZ6125"))
      (libsource (lib "eagle-import") (part "IP4234CZ6,125"))
    )
    (comp (ref "D4")
      (value "LED0805")
      (footprint "eagle-import:CHIPLED_0805")
      (libsource (lib "eagle-import") (part "LED0805"))
    )
    (comp (ref "Q1")
      (value "12MHz")
      (footprint "eagle-import:QS")
      (libsource (lib "eagle-import") (part "XTAL/S"))
    )
    (comp (ref "R1")
      (value "0")
      (footprint "eagle-import:R0603")
      (libsource (lib "eagle-import") (part "R-EU_R0603"))
    )
    (comp (ref "R3")
      (value "0")
      (footprint "eagle-import:R0603")
      (libsource (lib "eagle-import") (part "R-EU_R0603"))
    )
    (comp (ref "R4")
      (value "0")
      (footprint "eagle-import:R0603")
      (libsource (lib "eagle-import") (part "R-EU_R0603"))
    )
    (comp (ref "R8")
      (value "1k")
      (footprint "eagle-import:R0603")
      (libsource (lib "eagle-import") (part "R-EU_R0603"))
    )
    (comp (ref "R11")
      (value "10k")
      (footprint "eagle-import:R0603")
      (libsource (lib "eagle-import") (part "R-EU_R0603"))
    )
    (comp (ref "R12")
      (value "0")
      (footprint "eagle-import:R0603")
      (libsource (lib "eagle-import") (part "R-EU_R0603"))
    )
    (comp (ref "SV1")
      (value "FE05-1")
      (footprint "eagle-import:FE05-1")
      (libsource (lib "eagle-import") (part "FE05-1"))
    )
    (comp (ref "U3")
      (value "PIC18F14K50-I/SS")
      (footprint "eagle-import:SOP65P780X200-20N")
      (fields (field (name "MF") "Microchip"))
      (libsource (lib "eagle-import") (part "PIC18F14K50-I/SS"))
    )
    (comp (ref "X1")
      (value "MINI-USB-32005-201")
      (footprint "eagle-import:32005-201")
      (libsource (lib "eagle-import") (part "MINI-USB-32005-201"))
    )
  )
  (nets
    (net (code "1") (name "+1V2") (class "Default")
      (node (ref "B2") (pin "1") (pinfunction "P$1_1") (pintype "bidirectional"))
      (node (ref "B4") (pin "1") (pinfunction "P$1_1") (pintype "bidirectional"))
      (node (ref "C65") (pin "1") (pinfunction "1_1") (pintype "passive"))
      (node (ref "SJ3") (pin "2") (pinfunction "2_2") (pintype "passive"))
    )
    (net (code "2") (name "+2V5") (class "Default")
      (node (ref "B3") (pin "1") (pinfunction "P$1_1") (pintype "bidirectional"))
      (node (ref "C31") (pin "1") (pinfunction "1_1") (pintype "passive"))
      (node (ref "C60") (pin "1") (pinfunction "1_1") (pintype "passive"))
      (node (ref "R11") (pin "2") (pinfunction "2_2") (pintype "passive"))
      (node (ref "SJ6") (pin "2") (pinfunction "2_2") (pintype "passive"))
      (node (ref "SV1") (pin "2") (pinfunction "2_2") (pintype "passive"))
      (node (ref "U3") (pin "1") (pinfunction "VDD_1") (pintype "power_in"))
    )
    (net (code "3") (name "+3V3") (class "Default")
      (node (ref "B1") (pin "1") (pinfunction "P$1_1") (pintype "bidirectional"))
      (node (ref "B5") (pin "1") (pinfunction "P$1_1") (pintype "bidirectional"))
      (node (ref "B6") (pin "1") (pinfunction "P$1_1") (pintype "bidirectional"))
      (node (ref "C11") (pin "1") (pinfunction "1_1") (pintype "passive"))
      (node (ref "C30") (pin "2") (pinfunction "2_2") (pintype "passive"))
      (node (ref "C33") (pin "1") (pinfunction "1_1") (pintype "passive"))
      (node (ref "IC2") (pin "8") (pinfunction "VCC_8") (pintype "input"))
      (node (ref "R25") (pin "1") (pinfunction "1_1") (pintype "passive"))
      (node (ref "S1") (pin "3") (pinfunction "P$3_3") (pintype "bidirectional"))
      (node (ref "S1") (pin "4") (pinfunction "P$4_4") (pintype "bidirectional"))
      (node (ref "S2") (pin "3") (pinfunction "P$3_3") (pintype "bidirectional"))
      (node (ref "S2") (pin "4") (pinfunction "P$4_4") (pintype "bidirectional"))
      (node (ref "S3") (pin "3") (pinfunction "P$3_3") (pintype "bidirectional"))
      (node (ref "S3") (pin "4") (pinfunction "P$4_4") (pintype "bidirectional"))
      (node (ref "S4") (pin "3") (pinfunction "P$3_3") (pintype "bidirectional"))
      (node (ref "S4") (pin "4") (pinfunction "P$4_4") (pintype "bidirectional"))
      (node (ref "S5") (pin "3") (pinfunction "P$3_3") (pintype "bidirectional"))
      (node (ref "S5") (pin "4") (pinfunction "P$4_4") (pintype "bidirectional"))
      (node (ref "S6") (pin "1") (pinfunction "1_1") (pintype "passive"))
      (node (ref "S6") (pin "2") (pinfunction "2_2") (pintype "passive"))
      (node (ref "S6") (pin "3") (pinfunction "3_3") (pintype "passive"))
      (node (ref "S6") (pin "4") (pinfunction "4_4") (pintype "passive"))
      (node (ref "SJ2") (pin "1") (pinfunction "1_1") (pintype "passive"))
      (node (ref "SJ4") (pin "2") (pinfunction "2_2") (pintype "passive"))
      (node (ref "SV4") (pin "29") (pinfunction "29_29") (pintype "passive"))
      (node (ref "U4") (pin "3") (pinfunction "WP#_3") (pintype "bidirectional"))
      (node (ref "U4") (pin "8") (pinfunction "VCC_8") (pintype "bidirectional"))
    )
    (net (code "4") (name "+5V") (class "Default")
      (node (ref "C10") (pin "1") (pinfunction "1_1") (pintype "passive"))
      (node (ref "C17") (pin "1") (pinfunction "1_1") (pintype "passive"))
      (node (ref "C18") (pin "1") (pinfunction "1_1") (pintype "passive"))
      (node (ref "C21") (pin "+") (pinfunction "+_+") (pintype "passive"))
      (node (ref "C24") (pin "1") (pinfunction "1_1") (pintype "passive"))
      (node (ref "C50") (pin "1") (pinfunction "1_1") (pintype "passive"))
      (node (ref "C78") (pin "1") (pinfunction "1_1") (pintype "passive"))
      (node (ref "C79") (pin "1") (pinfunction "1_1") (pintype "passive"))
      (node (ref "C80") (pin "1") (pinfunction "1_1") (pintype "passive"))
      (node (ref "JP2") (pin "1") (pinfunction "1_1") (pintype "passive"))
      (node (ref "Q3") (pin "2") (pinfunction "S_2") (pintype "passive"))
      (node (ref "SV4") (pin "11") (pinfunction "11_11") (pintype "passive"))
      (node (ref "U$11") (pin "1") (pinfunction "EN_1") (pintype "bidirectional"))
      (node (ref "U$11") (pin "4") (pinfunction "VIN_4") (pintype "bidirectional"))
      (node (ref "U$3") (pin "1") (pinfunction "EN_1") (pintype "bidirectional"))
      (node (ref "U$3") (pin "4") (pinfunction "VIN_4") (pintype "bidirectional"))
      (node (ref "U$7") (pin "1") (pinfunction "EN_1") (pintype "bidirectional"))
      (node (ref "U$7") (pin "4") (pinfunction "VIN_4") (pintype "bidirectional"))
    )
    (net (code "5") (name "50MHZ_OUT") (class "Default")
      (node (ref "IC1") (pin "25") (pinfunction "CLK3_25") (pintype "input"))
      (node (ref "U2") (pin "3") (pinfunction "OUT_3") (pintype "bidirectional"))
    )
    (net (code "6") (name "CLK_SCL") (class "Default")
      (node (ref "IC1") (pin "66") (pinfunction "IO_25_66") (pintype "bidirectional"))
      (node (ref "R26") (pin "2") (pinfunction "2_2") (pintype "passive"))
      (node (ref "SV4") (pin "39") (pinfunction "39_39") (pintype "passive"))
      (node (ref "U1") (pin "4") (pinfunction "SCL_4") (pintype "bidirectional"))
    )
    (net (code "7") (name "CLK_SDA") (class "Default")
      (node (ref "IC1") (pin "65") (pinfunction "IO_24_65") (pintype "bidirectional"))
      (node (ref "R27") (pin "2") (pinfunction "2_2") (pintype "passive"))
      (node (ref "SV4") (pin "40") (pinfunction "40_40") (pintype "passive"))
      (node (ref "U1") (pin "5") (pinfunction "SDA_5") (pintype "bidirectional"))
    )
    (net (code "8") (name "D+") (class "Default")
      (node (ref "D2") (pin "3") (pinfunction "D+_I_3") (pintype "bidirectional"))
      (node (ref "SV1") (pin "4") (pinfunction "4_4") (pintype "passive"))
      (node (ref "U3") (pin "19") (pinfunction "RA0/AN0/CVREF/VREF-/C1IN+/INT0/PGD_19") (pintype "bidirectional"))
    )
    (net (code "9") (name "D-") (class "Default")
      (node (ref "D2") (pin "4") (pinfunction "D-_I_4") (pintype "bidirectional"))
      (node (ref "SV1") (pin "5") (pinfunction "5_5") (pintype "passive"))
      (node (ref "U3") (pin "18") (pinfunction "RA1/AN1/C12IN0-/VREF+/INT1/PGC_18") (pintype "bidirectional"))
    )
    (net (code "10") (name "FL_CE") (class "Default")
      (node (ref "IC1") (pin "8") (pinfunction "IO_3_8") (pintype "bidirectional"))
      (node (ref "U4") (pin "1") (pinfunction "CE#_1") (pintype "bidirectional"))
    )
    (net (code "11") (name "FL_CLK") (class "Default")
      (node (ref "IC1") (pin "12") (pinfunction "IO_6_12") (pintype "bidirectional"))
      (node (ref "U4") (pin "6") (pinfunction "SCK_6") (pintype "bidirectional"))
    )
    (net (code "12") (name "FL_SI") (class "Default")
      (node (ref "IC1") (pin "6") (pinfunction "IO_1_6") (pintype "bidirectional"))
      (node (ref "U4") (pin "5") (pinfunction "SI_5") (pintype "bidirectional"))
    )
    (net (code "13") (name "FL_SO") (class "Default")
      (node (ref "IC1") (pin "13") (pinfunction "IO_7_13") (pintype "bidirectional"))
      (node (ref "R37") (pin "2") (pinfunction "2_2") (pintype "passive"))
    )
    (net (code "14") (name "GND") (class "Default")
      (node (ref "C1") (pin "1") (pinfunction "1_1") (pintype "passive"))
      (node (ref "C10") (pin "2") (pinfunction "2_2") (pintype "passive"))
      (node (ref "C11") (pin "2") (pinfunction "2_2") (pintype "passive"))
      (node (ref "C12") (pin "2") (pinfunction "2_2") (pintype "passive"))
      (node (ref "C13") (pin "2") (pinfunction "2_2") (pintype "passive"))
      (node (ref "C14") (pin "2") (pinfunction "2_2") (pintype "passive"))
      (node (ref "C15") (pin "2") (pinfunction "2_2") (pintype "passive"))
      (node (ref "C16") (pin "2") (pinfunction "2_2") (pintype "passive"))
      (node (ref "C17") (pin "2") (pinfunction "2_2") (pintype "passive"))
      (node (ref "C18") (pin "2") (pinfunction "2_2") (pintype "passive"))
      (node (ref "C2") (pin "2") (pinfunction "2_2") (pintype "passive"))
      (node (ref "C20") (pin "2") (pinfunction "2_2") (pintype "passive"))
      (node (ref "C21") (pin "-") (pinfunction "-_-") (pintype "passive"))
      (node (ref "C22") (pin "2") (pinfunction "2_2") (pintype "passive"))
      (node (ref "C24") (pin "2") (pinfunction "2_2") (pintype "passive"))
      (node (ref "C25") (pin "2") (pinfunction "2_2") (pintype "passive"))
      (node (ref "C26") (pin "2") (pinfunction "2_2") (pintype "passive"))
      (node (ref "C27") (pin "1") (pinfunction "1_1") (pintype "passive"))
      (node (ref "C28") (pin "1") (pinfunction "1_1") (pintype "passive"))
      (node (ref "C29") (pin "2") (pinfunction "2_2") (pintype "passive"))
      (node (ref "C3") (pin "2") (pinfunction "2_2") (pintype "passive"))
      (node (ref "C30") (pin "1") (pinfunction "1_1") (pintype "passive"))
      (node (ref "C31") (pin "2") (pinfunction "2_2") (pintype "passive"))
      (node (ref "C32") (pin "2") (pinfunction "2_2") (pintype "passive"))
      (node (ref "C33") (pin "2") (pinfunction "2_2") (pintype "passive"))
      (node (ref "C34") (pin "2") (pinfunction "2_2") (pintype "passive"))
      (node (ref "C35") (pin "2") (pinfunction "2_2") (pintype "passive"))
      (node (ref "C36") (pin "2") (pinfunction "2_2") (pintype "passive"))
      (node (ref "C37") (pin "2") (pinfunction "2_2") (pintype "passive"))
      (node (ref "C38") (pin "2") (pinfunction "2_2") (pintype "passive"))
      (node (ref "C39") (pin "2") (pinfunction "2_2") (pintype "passive"))
      (node (ref "C4") (pin "1") (pinfunction "1_1") (pintype "passive"))
      (node (ref "C40") (pin "2") (pinfunction "2_2") (pintype "passive"))
      (node (ref "C41") (pin "2") (pinfunction "2_2") (pintype "passive"))
      (node (ref "C42") (pin "2") (pinfunction "2_2") (pintype "passive"))
      (node (ref "C43") (pin "2") (pinfunction "2_2") (pintype "passive"))
      (node (ref "C44") (pin "2") (pinfunction "2_2") (pintype "passive"))
      (node (ref "C45") (pin "2") (pinfunction "2_2") (pintype "passive"))
      (node (ref "C46") (pin "2") (pinfunction "2_2") (pintype "passive"))
      (node (ref "C47") (pin "2") (pinfunction "2_2") (pintype "passive"))
      (node (ref "C5") (pin "1") (pinfunction "1_1") (pintype "passive"))
      (node (ref "C50") (pin "2") (pinfunction "2_2") (pintype "passive"))
      (node (ref "C51") (pin "2") (pinfunction "2_2") (pintype "passive"))
      (node (ref "C52") (pin "2") (pinfunction "2_2") (pintype "passive"))
      (node (ref "C53") (pin "2") (pinfunction "2_2") (pintype "passive"))
      (node (ref "C54") (pin "2") (pinfunction "2_2") (pintype "passive"))
      (node (ref "C55") (pin "2") (pinfunction "2_2") (pintype "passive"))
      (node (ref "C58") (pin "2") (pinfunction "2_2") (pintype "passive"))
      (node (ref "C59") (pin "2") (pinfunction "2_2") (pintype "passive"))
      (node (ref "C6") (pin "1") (pinfunction "1_1") (pintype "passive"))
      (node (ref "C60") (pin "2") (pinfunction "2_2") (pintype "passive"))
      (node (ref "C61") (pin "2") (pinfunction "2_2") (pintype "passive"))
      (node (ref "C64") (pin "2") (pinfunction "2_2") (pintype "passive"))
      (node (ref "C65") (pin "2") (pinfunction "2_2") (pintype "passive"))
      (node (ref "C7") (pin "1") (pinfunction "1_1") (pintype "passive"))
      (node (ref "C78") (pin "2") (pinfunction "2_2") (pintype "passive"))
      (node (ref "C79") (pin "2") (pinfunction "2_2") (pintype "passive"))
      (node (ref "C8") (pin "2") (pinfunction "2_2") (pintype "passive"))
      (node (ref "C80") (pin "2") (pinfunction "2_2") (pintype "passive"))
      (node (ref "C81") (pin "1") (pinfunction "1_1") (pintype "passive"))
      (node (ref "C82") (pin "1") (pinfunction "1_1") (pintype "passive"))
      (node (ref "D1") (pin "A") (pinfunction "A_A") (pintype "passive"))
      (node (ref "D2") (pin "2") (pinfunction "GND_2") (pintype "bidirectional"))
      (node (ref "D3") (pin "2") (pinfunction "GND_2") (pintype "bidirectional"))
      (node (ref "D4") (pin "C") (pinfunction "C_C") (pintype "passive"))
      (node (ref "H1") (pin "B2,8") (pinfunction "MOUNT_B2,8") (pintype "passive"))
      (node (ref "IC1") (pin "104") (pinfunction "GND_13_104") (pintype "power_in"))
      (node (ref "IC1") (pin "108") (pinfunction "GNDA2_108") (pintype "power_in"))
      (node (ref "IC1") (pin "110") (pinfunction "GND_14_110") (pintype "power_in"))
      (node (ref "IC1") (pin "118") (pinfunction "GND_15_118") (pintype "power_in"))
      (node (ref "IC1") (pin "123") (pinfunction "GND_16_123") (pintype "power_in"))
      (node (ref "IC1") (pin "131") (pinfunction "GND_17_131") (pintype "power_in"))
      (node (ref "IC1") (pin "140") (pinfunction "GND_18_140") (pintype "power_in"))
      (node (ref "IC1") (pin "145") (pinfunction "GND_19_145") (pintype "power_in"))
      (node (ref "IC1") (pin "19") (pinfunction "GND_2_19") (pintype "power_in"))
      (node (ref "IC1") (pin "2") (pinfunction "GNDA3_2") (pintype "power_in"))
      (node (ref "IC1") (pin "21") (pinfunction "NCE_21") (pintype "input"))
      (node (ref "IC1") (pin "27") (pinfunction "GND_3_27") (pintype "power_in"))
      (node (ref "IC1") (pin "30") (pinfunction "GND_4_30") (pintype "power_in"))
      (node (ref "IC1") (pin "36") (pinfunction "GNDA1_36") (pintype "power_in"))
      (node (ref "IC1") (pin "4") (pinfunction "GND_1_4") (pintype "power_in"))
      (node (ref "IC1") (pin "41") (pinfunction "GND_5_41") (pintype "power_in"))
      (node (ref "IC1") (pin "48") (pinfunction "GND_6_48") (pintype "power_in"))
      (node (ref "IC1") (pin "57") (pinfunction "GND_7_57") (pintype "power_in"))
      (node (ref "IC1") (pin "63") (pinfunction "GND_8_63") (pintype "power_in"))
      (node (ref "IC1") (pin "64") (pinfunction "GND_9_64") (pintype "power_in"))
      (node (ref "IC1") (pin "74") (pinfunction "GNDA4_74") (pintype "power_in"))
      (node (ref "IC1") (pin "79") (pinfunction "GND_10_79") (pintype "power_in"))
      (node (ref "IC1") (pin "82") (pinfunction "GND_11_82") (pintype "power_in"))
      (node (ref "IC1") (pin "95") (pinfunction "GND_12_95") (pintype "power_in"))
      (node (ref "IC1") (pin "96") (pinfunction "MSEL1_96") (pintype "input"))
      (node (ref "IC2") (pin "5") (pinfunction "GND_5") (pintype "input"))
      (node (ref "JP1") (pin "1") (pinfunction "1_1") (pintype "passive"))
      (node (ref "LED0") (pin "C") (pinfunction "C_C") (pintype "passive"))
      (node (ref "LED1") (pin "C") (pinfunction "C_C") (pintype "passive"))
      (node (ref "LED2") (pin "C") (pinfunction "C_C") (pintype "passive"))
      (node (ref "LED3") (pin "C") (pinfunction "C_C") (pintype "passive"))
      (node (ref "LED4") (pin "C") (pinfunction "C_C") (pintype "passive"))
      (node (ref "LED5") (pin "C") (pinfunction "C_C") (pintype "passive"))
      (node (ref "LED6") (pin "C") (pinfunction "C_C") (pintype "passive"))
      (node (ref "LED7") (pin "C") (pinfunction "C_C") (pintype "passive"))
      (node (ref "LED8") (pin "4") (pinfunction "BLUE_C_4") (pintype "bidirectional"))
      (node (ref "LED8") (pin "5") (pinfunction "RED_C_5") (pintype "bidirectional"))
      (node (ref "LED8") (pin "6") (pinfunction "GREEN_C_6") (pintype "bidirectional"))
      (node (ref "Q3") (pin "1") (pinfunction "G_1") (pintype "passive"))
      (node (ref "R18") (pin "1") (pinfunction "1_1") (pintype "passive"))
      (node (ref "R20") (pin "1") (pinfunction "1_1") (pintype "passive"))
      (node (ref "R24") (pin "1") (pinfunction "1_1") (pintype "passive"))
      (node (ref "R29") (pin "1") (pinfunction "1_1") (pintype "passive"))
      (node (ref "R5") (pin "1") (pinfunction "1_1") (pintype "passive"))
      (node (ref "R6") (pin "1") (pinfunction "1_1") (pintype "passive"))
      (node (ref "RN13") (pin "1") (pinfunction "1_1") (pintype "passive"))
      (node (ref "RN13") (pin "2") (pinfunction "2_2") (pintype "passive"))
      (node (ref "RN13") (pin "3") (pinfunction "3_3") (pintype "passive"))
      (node (ref "RN13") (pin "4") (pinfunction "4_4") (pintype "passive"))
      (node (ref "RN2") (pin "5") (pinfunction "5_5") (pintype "passive"))
      (node (ref "RN2") (pin "6") (pinfunction "6_6") (pintype "passive"))
      (node (ref "RN2") (pin "7") (pinfunction "7_7") (pintype "passive"))
      (node (ref "RN2") (pin "8") (pinfunction "8_8") (pintype "passive"))
      (node (ref "RS485") (pin "2") (pinfunction "KL_2") (pintype "passive"))
      (node (ref "SJ2") (pin "3") (pinfunction "3_3") (pintype "passive"))
      (node (ref "SV1") (pin "3") (pinfunction "3_3") (pintype "passive"))
      (node (ref "SV4") (pin "12") (pinfunction "12_12") (pintype "passive"))
      (node (ref "SV4") (pin "30") (pinfunction "30_30") (pintype "passive"))
      (node (ref "U$1") (pin "P$11") (pinfunction "CLOCKSHIELD_P$11") (pintype "bidirectional"))
      (node (ref "U$1") (pin "P$17") (pinfunction "CECGND_P$17") (pintype "bidirectional"))
      (node (ref "U$1") (pin "P$2") (pinfunction "DATA2SHIELD_P$2") (pintype "bidirectional"))
      (node (ref "U$1") (pin "P$5") (pinfunction "DATA1SHIELD_P$5") (pintype "bidirectional"))
      (node (ref "U$1") (pin "P$8") (pinfunction "DATA0SHIELD_P$8") (pintype "bidirectional"))
      (node (ref "U$11") (pin "2") (pinfunction "GND_2") (pintype "bidirectional"))
      (node (ref "U$3") (pin "2") (pinfunction "GND_2") (pintype "bidirectional"))
      (node (ref "U$7") (pin "2") (pinfunction "GND_2") (pintype "bidirectional"))
      (node (ref "U1") (pin "8") (pinfunction "GND_8") (pintype "power_in"))
      (node (ref "U2") (pin "2") (pinfunction "GND_2") (pintype "bidirectional"))
      (node (ref "U3") (pin "20") (pinfunction "VSS_20") (pintype "power_in"))
      (node (ref "U4") (pin "4") (pinfunction "GND_4") (pintype "bidirectional"))
      (node (ref "X1") (pin "5") (pinfunction "5_5") (pintype "passive"))
      (node (ref "X2") (pin "5") (pinfunction "5_5") (pintype "passive"))
    )
    (net (code "15") (name "GPIO_1") (class "Default")
      (node (ref "IC1") (pin "144") (pinfunction "IO_63_144") (pintype "bidirectional"))
      (node (ref "SV4") (pin "1") (pinfunction "1_1") (pintype "passive"))
    )
    (net (code "16") (name "GPIO_2") (class "Default")
      (node (ref "IC1") (pin "143") (pinfunction "IO_62_143") (pintype "bidirectional"))
      (node (ref "SV4") (pin "2") (pinfunction "2_2") (pintype "passive"))
    )
    (net (code "17") (name "GPIO_3") (class "Default")
      (node (ref "IC1") (pin "142") (pinfunction "IO_61_142") (pintype "bidirectional"))
      (node (ref "SV4") (pin "3") (pinfunction "3_3") (pintype "passive"))
    )
    (net (code "18") (name "GPIO_4") (class "Default")
      (node (ref "IC1") (pin "141") (pinfunction "IO_60_141") (pintype "bidirectional"))
      (node (ref "SV4") (pin "4") (pinfunction "4_4") (pintype "passive"))
    )
    (net (code "19") (name "GPIO_5") (class "Default")
      (node (ref "IC1") (pin "137") (pinfunction "IO_59_137") (pintype "bidirectional"))
      (node (ref "SV4") (pin "5") (pinfunction "5_5") (pintype "passive"))
    )
    (net (code "20") (name "GPIO_6") (class "Default")
      (node (ref "IC1") (pin "136") (pinfunction "IO_58_136") (pintype "bidirectional"))
      (node (ref "SV4") (pin "6") (pinfunction "6_6") (pintype "passive"))
    )
    (net (code "21") (name "GPIO_11") (class "Default")
      (node (ref "IC1") (pin "125") (pinfunction "IO_53_125") (pintype "bidirectional"))
      (node (ref "SV4") (pin "13") (pinfunction "13_13") (pintype "passive"))
    )
    (net (code "22") (name "GPIO_12") (class "Default")
      (node (ref "IC1") (pin "121") (pinfunction "IO_52_121") (pintype "bidirectional"))
      (node (ref "SV4") (pin "14") (pinfunction "14_14") (pintype "passive"))
    )
    (net (code "23") (name "GPIO_13") (class "Default")
      (node (ref "IC1") (pin "120") (pinfunction "IO_51_120") (pintype "bidirectional"))
      (node (ref "SV4") (pin "15") (pinfunction "15_15") (pintype "passive"))
    )
    (net (code "24") (name "GPIO_14") (class "Default")
      (node (ref "IC1") (pin "119") (pinfunction "IO_50_119") (pintype "bidirectional"))
      (node (ref "SV4") (pin "16") (pinfunction "16_16") (pintype "passive"))
    )
    (net (code "25") (name "GPIO_15") (class "Default")
      (node (ref "IC1") (pin "115") (pinfunction "IO_49_115") (pintype "bidirectional"))
      (node (ref "SV4") (pin "17") (pinfunction "17_17") (pintype "passive"))
    )
    (net (code "26") (name "GPIO_16") (class "Default")
      (node (ref "IC1") (pin "114") (pinfunction "IO_48_114") (pintype "bidirectional"))
      (node (ref "SV4") (pin "18") (pinfunction "18_18") (pintype "passive"))
    )
    (net (code "27") (name "GPIO_17") (class "Default")
      (node (ref "IC1") (pin "113") (pinfunction "IO_47_113") (pintype "bidirectional"))
      (node (ref "SV4") (pin "19") (pinfunction "19_19") (pintype "passive"))
    )
    (net (code "28") (name "GPIO_18") (class "Default")
      (node (ref "IC1") (pin "112") (pinfunction "IO_46_112") (pintype "bidirectional"))
      (node (ref "SV4") (pin "20") (pinfunction "20_20") (pintype "passive"))
    )
    (net (code "29") (name "GPIO_19") (class "Default")
      (node (ref "IC1") (pin "111") (pinfunction "IO_45_111") (pintype "bidirectional"))
      (node (ref "SV4") (pin "21") (pinfunction "21_21") (pintype "passive"))
    )
    (net (code "30") (name "GPIO_20") (class "Default")
      (node (ref "IC1") (pin "106") (pinfunction "IO_44_106") (pintype "bidirectional"))
      (node (ref "SV4") (pin "22") (pinfunction "22_22") (pintype "passive"))
    )
    (net (code "31") (name "GPIO_21") (class "Default")
      (node (ref "IC1") (pin "105") (pinfunction "IO_43_105") (pintype "bidirectional"))
      (node (ref "SV4") (pin "23") (pinfunction "23_23") (pintype "passive"))
    )
    (net (code "32") (name "GPIO_22") (class "Default")
      (node (ref "IC1") (pin "100") (pinfunction "IO_40_100") (pintype "bidirectional"))
      (node (ref "SV4") (pin "24") (pinfunction "24_24") (pintype "passive"))
    )
    (net (code "33") (name "GPIO_27") (class "Default")
      (node (ref "IC1") (pin "80") (pinfunction "IO_33_80") (pintype "bidirectional"))
      (node (ref "SV4") (pin "31") (pinfunction "31_31") (pintype "passive"))
    )
    (net (code "34") (name "GPIO_28") (class "Default")
      (node (ref "IC1") (pin "77") (pinfunction "IO_32_77") (pintype "bidirectional"))
      (node (ref "SV4") (pin "32") (pinfunction "32_32") (pintype "passive"))
    )
    (net (code "35") (name "GPIO_29") (class "Default")
      (node (ref "IC1") (pin "76") (pinfunction "IO_31_76") (pintype "bidirectional"))
      (node (ref "SV4") (pin "33") (pinfunction "33_33") (pintype "passive"))
    )
    (net (code "36") (name "GPIO_30") (class "Default")
      (node (ref "IC1") (pin "72") (pinfunction "IO_30_72") (pintype "bidirectional"))
      (node (ref "SV4") (pin "34") (pinfunction "34_34") (pintype "passive"))
    )
    (net (code "37") (name "GPIO_31") (class "Default")
      (node (ref "IC1") (pin "71") (pinfunction "IO_29_71") (pintype "bidirectional"))
      (node (ref "SV4") (pin "35") (pinfunction "35_35") (pintype "passive"))
    )
    (net (code "38") (name "GPIO_32") (class "Default")
      (node (ref "IC1") (pin "69") (pinfunction "IO_28_69") (pintype "bidirectional"))
      (node (ref "SV4") (pin "36") (pinfunction "36_36") (pintype "passive"))
    )
    (net (code "39") (name "GPIO_33") (class "Default")
      (node (ref "IC1") (pin "68") (pinfunction "IO_27_68") (pintype "bidirectional"))
      (node (ref "SV4") (pin "37") (pinfunction "37_37") (pintype "passive"))
    )
    (net (code "40") (name "GPIO_34") (class "Default")
      (node (ref "IC1") (pin "67") (pinfunction "IO_26_67") (pintype "bidirectional"))
      (node (ref "SV4") (pin "38") (pinfunction "38_38") (pintype "passive"))
    )
    (net (code "41") (name "GPI_7") (class "Default")
      (node (ref "IC1") (pin "129") (pinfunction "CLK11_129") (pintype "input"))
      (node (ref "SV4") (pin "7") (pinfunction "7_7") (pintype "passive"))
    )
    (net (code "42") (name "GPI_8") (class "Default")
      (node (ref "IC1") (pin "128") (pinfunction "CLK10_128") (pintype "input"))
      (node (ref "SV4") (pin "8") (pinfunction "8_8") (pintype "passive"))
    )
    (net (code "43") (name "GPI_9") (class "Default")
      (node (ref "IC1") (pin "127") (pinfunction "CLK9_127") (pintype "input"))
      (node (ref "SV4") (pin "9") (pinfunction "9_9") (pintype "passive"))
    )
    (net (code "44") (name "GPI_10") (class "Default")
      (node (ref "IC1") (pin "126") (pinfunction "CLK8_126") (pintype "input"))
      (node (ref "SV4") (pin "10") (pinfunction "10_10") (pintype "passive"))
    )
    (net (code "45") (name "GPI_23") (class "Default")
      (node (ref "IC1") (pin "91") (pinfunction "CLK4_91") (pintype "input"))
      (node (ref "SV4") (pin "25") (pinfunction "25_25") (pintype "passive"))
    )
    (net (code "46") (name "GPI_24") (class "Default")
      (node (ref "IC1") (pin "90") (pinfunction "CLK5_90") (pintype "input"))
      (node (ref "SV4") (pin "26") (pinfunction "26_26") (pintype "passive"))
    )
    (net (code "47") (name "GPI_25") (class "Default")
      (node (ref "IC1") (pin "89") (pinfunction "CLK6_89") (pintype "input"))
      (node (ref "SV4") (pin "27") (pinfunction "27_27") (pintype "passive"))
    )
    (net (code "48") (name "GPI_26") (class "Default")
      (node (ref "IC1") (pin "88") (pinfunction "CLK7_88") (pintype "input"))
      (node (ref "SV4") (pin "28") (pinfunction "28_28") (pintype "passive"))
    )
    (net (code "49") (name "HDMI_CEC") (class "Default")
      (node (ref "IC1") (pin "83") (pinfunction "IO_34_83") (pintype "bidirectional"))
      (node (ref "U$1") (pin "P$13") (pinfunction "CEC_P$13") (pintype "bidirectional"))
    )
    (net (code "50") (name "HDMI_CLKN") (class "Default")
      (node (ref "IC1") (pin "98") (pinfunction "IO_38_98") (pintype "bidirectional"))
      (node (ref "U$1") (pin "P$12") (pinfunction "CLOCK-_P$12") (pintype "bidirectional"))
    )
    (net (code "51") (name "HDMI_CLKP") (class "Default")
      (node (ref "IC1") (pin "99") (pinfunction "IO_39_99") (pintype "bidirectional"))
      (node (ref "U$1") (pin "P$10") (pinfunction "CLOCK+_P$10") (pintype "bidirectional"))
    )
    (net (code "52") (name "HDMI_DATA0N") (class "Default")
      (node (ref "IC1") (pin "101") (pinfunction "IO_41_101") (pintype "bidirectional"))
      (node (ref "U$1") (pin "P$9") (pinfunction "DATA0-_P$9") (pintype "bidirectional"))
    )
    (net (code "53") (name "HDMI_DATA0P") (class "Default")
      (node (ref "IC1") (pin "103") (pinfunction "IO_42_103") (pintype "bidirectional"))
      (node (ref "U$1") (pin "P$7") (pinfunction "DATA0+_P$7") (pintype "bidirectional"))
    )
    (net (code "54") (name "HDMI_DATA1N") (class "Default")
      (node (ref "IC1") (pin "132") (pinfunction "IO_54_132") (pintype "bidirectional"))
      (node (ref "U$1") (pin "P$6") (pinfunction "DATA1-_P$6") (pintype "bidirectional"))
    )
    (net (code "55") (name "HDMI_DATA1P") (class "Default")
      (node (ref "IC1") (pin "133") (pinfunction "IO_55_133") (pintype "bidirectional"))
      (node (ref "U$1") (pin "P$4") (pinfunction "DATA1+_P$4") (pintype "bidirectional"))
    )
    (net (code "56") (name "HDMI_DATA2N") (class "Default")
      (node (ref "IC1") (pin "134") (pinfunction "IO_56_134") (pintype "bidirectional"))
      (node (ref "U$1") (pin "P$3") (pinfunction "DATA2-_P$3") (pintype "bidirectional"))
    )
    (net (code "57") (name "HDMI_DATA2P") (class "Default")
      (node (ref "IC1") (pin "135") (pinfunction "IO_57_135") (pintype "bidirectional"))
      (node (ref "U$1") (pin "P$1") (pinfunction "DATA2+_P$1") (pintype "bidirectional"))
    )
    (net (code "58") (name "LED_0") (class "Default")
      (node (ref "IC1") (pin "39") (pinfunction "IO_12_39") (pintype "bidirectional"))
      (node (ref "RN6") (pin "4") (pinfunction "4_4") (pintype "passive"))
    )
    (net (code "59") (name "LED_1") (class "Default")
      (node (ref "IC1") (pin "42") (pinfunction "IO_13_42") (pintype "bidirectional"))
      (node (ref "RN6") (pin "3") (pinfunction "3_3") (pintype "passive"))
    )
    (net (code "60") (name "LED_2") (class "Default")
      (node (ref "IC1") (pin "43") (pinfunction "IO_14_43") (pintype "bidirectional"))
      (node (ref "RN6") (pin "2") (pinfunction "2_2") (pintype "passive"))
    )
    (net (code "61") (name "LED_3") (class "Default")
      (node (ref "IC1") (pin "44") (pinfunction "IO_15_44") (pintype "bidirectional"))
      (node (ref "RN6") (pin "1") (pinfunction "1_1") (pintype "passive"))
    )
    (net (code "62") (name "LED_4") (class "Default")
      (node (ref "IC1") (pin "46") (pinfunction "IO_16_46") (pintype "bidirectional"))
      (node (ref "RN5") (pin "4") (pinfunction "4_4") (pintype "passive"))
    )
    (net (code "63") (name "LED_5") (class "Default")
      (node (ref "IC1") (pin "49") (pinfunction "IO_17_49") (pintype "bidirectional"))
      (node (ref "RN5") (pin "3") (pinfunction "3_3") (pintype "passive"))
    )
    (net (code "64") (name "LED_6") (class "Default")
      (node (ref "IC1") (pin "50") (pinfunction "IO_18_50") (pintype "bidirectional"))
      (node (ref "RN5") (pin "2") (pinfunction "2_2") (pintype "passive"))
    )
    (net (code "65") (name "LED_7") (class "Default")
      (node (ref "IC1") (pin "51") (pinfunction "IO_19_51") (pintype "bidirectional"))
      (node (ref "RN5") (pin "1") (pinfunction "1_1") (pintype "passive"))
    )
    (net (code "66") (name "N$87") (class "Default")
      (node (ref "IC1") (pin "109") (pinfunction "VCCD_PLL2_109") (pintype "power_in"))
    )
    (net (code "67") (name "Net-(B5-P$2)") (class "Default")
      (node (ref "B5") (pin "2") (pinfunction "P$2_2") (pintype "bidirectional"))
      (node (ref "C27") (pin "2") (pinfunction "2_2") (pintype "passive"))
      (node (ref "U2") (pin "1") (pinfunction "EN_1") (pintype "bidirectional"))
      (node (ref "U2") (pin "4") (pinfunction "VCC_4") (pintype "bidirectional"))
    )
    (net (code "68") (name "Net-(B6-P$2)") (class "Default")
      (node (ref "B6") (pin "2") (pinfunction "P$2_2") (pintype "bidirectional"))
      (node (ref "C28") (pin "2") (pinfunction "2_2") (pintype "passive"))
      (node (ref "C29") (pin "1") (pinfunction "1_1") (pintype "passive"))
      (node (ref "R26") (pin "1") (pinfunction "1_1") (pintype "passive"))
      (node (ref "R27") (pin "1") (pinfunction "1_1") (pintype "passive"))
      (node (ref "U1") (pin "1") (pinfunction "VDD_1") (pintype "power_in"))
      (node (ref "U1") (pin "7") (pinfunction "VDDO_7") (pintype "power_in"))
    )
    (net (code "69") (name "Net-(C14-Pad1)") (class "Default")
      (node (ref "C14") (pin "1") (pinfunction "1_1") (pintype "passive"))
      (node (ref "C15") (pin "1") (pinfunction "1_1") (pintype "passive"))
      (node (ref "C16") (pin "1") (pinfunction "1_1") (pintype "passive"))
      (node (ref "C20") (pin "1") (pinfunction "1_1") (pintype "passive"))
      (node (ref "C22") (pin "1") (pinfunction "1_1") (pintype "passive"))
      (node (ref "C23") (pin "1") (pinfunction "1_1") (pintype "passive"))
      (node (ref "L4") (pin "P$1") (pinfunction "P$1_P$1") (pintype "bidirectional"))
      (node (ref "R28") (pin "2") (pinfunction "2_2") (pintype "passive"))
      (node (ref "SJ3") (pin "1") (pinfunction "1_1") (pintype "passive"))
    )
    (net (code "70") (name "Net-(C25-Pad1)") (class "Default")
      (node (ref "C25") (pin "1") (pinfunction "1_1") (pintype "passive"))
      (node (ref "C26") (pin "1") (pinfunction "1_1") (pintype "passive"))
      (node (ref "C41") (pin "1") (pinfunction "1_1") (pintype "passive"))
      (node (ref "C42") (pin "1") (pinfunction "1_1") (pintype "passive"))
      (node (ref "C43") (pin "1") (pinfunction "1_1") (pintype "passive"))
      (node (ref "C9") (pin "1") (pinfunction "1_1") (pintype "passive"))
      (node (ref "L2") (pin "P$1") (pinfunction "P$1_P$1") (pintype "bidirectional"))
      (node (ref "R19") (pin "2") (pinfunction "2_2") (pintype "passive"))
      (node (ref "SJ4") (pin "1") (pinfunction "1_1") (pintype "passive"))
    )
    (net (code "71") (name "Net-(C49-Pad1)") (class "Default")
      (node (ref "C49") (pin "1") (pinfunction "1_1") (pintype "passive"))
      (node (ref "C51") (pin "1") (pinfunction "1_1") (pintype "passive"))
      (node (ref "C52") (pin "1") (pinfunction "1_1") (pintype "passive"))
      (node (ref "C53") (pin "1") (pinfunction "1_1") (pintype "passive"))
      (node (ref "C54") (pin "1") (pinfunction "1_1") (pintype "passive"))
      (node (ref "C55") (pin "1") (pinfunction "1_1") (pintype "passive"))
      (node (ref "L3") (pin "P$1") (pinfunction "P$1_P$1") (pintype "bidirectional"))
      (node (ref "R2") (pin "2") (pinfunction "2_2") (pintype "passive"))
      (node (ref "SJ6") (pin "1") (pinfunction "1_1") (pintype "passive"))
    )
    (net (code "72") (name "Net-(D2-D+_O)") (class "Default")
      (node (ref "D2") (pin "1") (pinfunction "D+_O_1") (pintype "bidirectional"))
      (node (ref "X1") (pin "3") (pinfunction "3_3") (pintype "passive"))
    )
    (net (code "73") (name "Net-(D2-D-_O)") (class "Default")
      (node (ref "D2") (pin "6") (pinfunction "D-_O_6") (pintype "bidirectional"))
      (node (ref "X1") (pin "2") (pinfunction "2_2") (pintype "passive"))
    )
    (net (code "74") (name "Net-(D3-D+_O)") (class "Default")
      (node (ref "D3") (pin "1") (pinfunction "D+_O_1") (pintype "bidirectional"))
      (node (ref "X2") (pin "3") (pinfunction "3_3") (pintype "passive"))
    )
    (net (code "75") (name "Net-(D3-D-_O)") (class "Default")
      (node (ref "D3") (pin "6") (pinfunction "D-_O_6") (pintype "bidirectional"))
      (node (ref "X2") (pin "2") (pinfunction "2_2") (pintype "passive"))
    )
    (net (code "76") (name "Net-(D3-VCC)") (class "Default")
      (node (ref "D3") (pin "5") (pinfunction "VCC_5") (pintype "bidirectional"))
      (node (ref "JP2") (pin "2") (pinfunction "2_2") (pintype "passive"))
      (node (ref "X2") (pin "1") (pinfunction "1_1") (pintype "passive"))
    )
    (net (code "77") (name "Net-(D4-PadA)") (class "Default")
      (node (ref "D4") (pin "A") (pinfunction "A_A") (pintype "passive"))
      (node (ref "R8") (pin "1") (pinfunction "1_1") (pintype "passive"))
    )
    (net (code "78") (name "Net-(IC1-CONF_DONE)") (class "Default")
      (node (ref "IC1") (pin "92") (pinfunction "CONF_DONE_92") (pintype "bidirectional"))
      (node (ref "R36") (pin "1") (pinfunction "1_1") (pintype "passive"))
    )
    (net (code "79") (name "Net-(IC1-NCONFIG)") (class "Default")
      (node (ref "IC1") (pin "14") (pinfunction "NCONFIG_14") (pintype "input"))
      (node (ref "R34") (pin "2") (pinfunction "2_2") (pintype "passive"))
    )
    (net (code "80") (name "Net-(IC1-NSTATUS)") (class "Default")
      (node (ref "IC1") (pin "9") (pinfunction "NSTATUS_9") (pintype "bidirectional"))
      (node (ref "R33") (pin "2") (pinfunction "2_2") (pintype "passive"))
    )
    (net (code "81") (name "Net-(IC2-A)") (class "Default")
      (node (ref "IC2") (pin "6") (pinfunction "A_6") (pintype "input"))
      (node (ref "R22") (pin "1") (pinfunction "1_1") (pintype "passive"))
      (node (ref "R23") (pin "1") (pinfunction "1_1") (pintype "passive"))
    )
    (net (code "82") (name "Net-(IC2-B)") (class "Default")
      (node (ref "IC2") (pin "7") (pinfunction "B_7") (pintype "input"))
      (node (ref "R21") (pin "1") (pinfunction "1_1") (pintype "passive"))
      (node (ref "R23") (pin "2") (pinfunction "2_2") (pintype "passive"))
    )
    (net (code "83") (name "Net-(LED0-PadA)") (class "Default")
      (node (ref "LED0") (pin "A") (pinfunction "A_A") (pintype "passive"))
      (node (ref "RN6") (pin "5") (pinfunction "5_5") (pintype "passive"))
    )
    (net (code "84") (name "Net-(LED1-PadA)") (class "Default")
      (node (ref "LED1") (pin "A") (pinfunction "A_A") (pintype "passive"))
      (node (ref "RN6") (pin "6") (pinfunction "6_6") (pintype "passive"))
    )
    (net (code "85") (name "Net-(LED2-PadA)") (class "Default")
      (node (ref "LED2") (pin "A") (pinfunction "A_A") (pintype "passive"))
      (node (ref "RN6") (pin "7") (pinfunction "7_7") (pintype "passive"))
    )
    (net (code "86") (name "Net-(LED3-PadA)") (class "Default")
      (node (ref "LED3") (pin "A") (pinfunction "A_A") (pintype "passive"))
      (node (ref "RN6") (pin "8") (pinfunction "8_8") (pintype "passive"))
    )
    (net (code "87") (name "Net-(LED4-PadA)") (class "Default")
      (node (ref "LED4") (pin "A") (pinfunction "A_A") (pintype "passive"))
      (node (ref "RN5") (pin "5") (pinfunction "5_5") (pintype "passive"))
    )
    (net (code "88") (name "Net-(LED5-PadA)") (class "Default")
      (node (ref "LED5") (pin "A") (pinfunction "A_A") (pintype "passive"))
      (node (ref "RN5") (pin "6") (pinfunction "6_6") (pintype "passive"))
    )
    (net (code "89") (name "Net-(LED6-PadA)") (class "Default")
      (node (ref "LED6") (pin "A") (pinfunction "A_A") (pintype "passive"))
      (node (ref "RN5") (pin "7") (pinfunction "7_7") (pintype "passive"))
    )
    (net (code "90") (name "Net-(LED7-PadA)") (class "Default")
      (node (ref "LED7") (pin "A") (pinfunction "A_A") (pintype "passive"))
      (node (ref "RN5") (pin "8") (pinfunction "8_8") (pintype "passive"))
    )
    (net (code "91") (name "Net-(LED8-BLUE_A)") (class "Default")
      (node (ref "LED8") (pin "3") (pinfunction "BLUE_A_3") (pintype "bidirectional"))
      (node (ref "RN1") (pin "1") (pinfunction "1_1") (pintype "passive"))
    )
    (net (code "92") (name "Net-(LED8-GREEN_A)") (class "Default")
      (node (ref "LED8") (pin "1") (pinfunction "GREEN_A_1") (pintype "bidirectional"))
      (node (ref "RN1") (pin "3") (pinfunction "3_3") (pintype "passive"))
    )
    (net (code "93") (name "Net-(LED8-RED_A)") (class "Default")
      (node (ref "LED8") (pin "2") (pinfunction "RED_A_2") (pintype "bidirectional"))
      (node (ref "RN1") (pin "2") (pinfunction "2_2") (pintype "passive"))
    )
    (net (code "94") (name "Net-(R35-Pad2)") (class "Default")
      (node (ref "R35") (pin "2") (pinfunction "2_2") (pintype "passive"))
      (node (ref "X2") (pin "4") (pinfunction "4_4") (pintype "passive"))
    )
    (net (code "95") (name "Net-(RN2-Pad1)") (class "Default")
      (node (ref "RN2") (pin "1") (pinfunction "1_1") (pintype "passive"))
      (node (ref "RN3") (pin "1") (pinfunction "1_1") (pintype "passive"))
      (node (ref "S6") (pin "5") (pinfunction "5_5") (pintype "passive"))
    )
    (net (code "96") (name "Net-(RN2-Pad2)") (class "Default")
      (node (ref "RN2") (pin "2") (pinfunction "2_2") (pintype "passive"))
      (node (ref "RN3") (pin "2") (pinfunction "2_2") (pintype "passive"))
      (node (ref "S6") (pin "6") (pinfunction "6_6") (pintype "passive"))
    )
    (net (code "97") (name "Net-(RN2-Pad3)") (class "Default")
      (node (ref "RN2") (pin "3") (pinfunction "3_3") (pintype "passive"))
      (node (ref "RN3") (pin "3") (pinfunction "3_3") (pintype "passive"))
      (node (ref "S6") (pin "7") (pinfunction "7_7") (pintype "passive"))
    )
    (net (code "98") (name "Net-(RN2-Pad4)") (class "Default")
      (node (ref "RN2") (pin "4") (pinfunction "4_4") (pintype "passive"))
      (node (ref "RN3") (pin "4") (pinfunction "4_4") (pintype "passive"))
      (node (ref "S6") (pin "8") (pinfunction "8_8") (pintype "passive"))
    )
    (net (code "99") (name "Net-(RS485A-KL)") (class "Default")
      (node (ref "R22") (pin "2") (pinfunction "2_2") (pintype "passive"))
      (node (ref "RS485") (pin "1") (pinfunction "KL_1") (pintype "passive"))
    )
    (net (code "100") (name "Net-(RS485C-KL)") (class "Default")
      (node (ref "R21") (pin "2") (pinfunction "2_2") (pintype "passive"))
      (node (ref "RS485") (pin "3") (pinfunction "KL_3") (pintype "passive"))
    )
    (net (code "101") (name "Net-(S1-P$1)") (class "Default")
      (node (ref "C7") (pin "2") (pinfunction "2_2") (pintype "passive"))
      (node (ref "RN13") (pin "8") (pinfunction "8_8") (pintype "passive"))
      (node (ref "RN7") (pin "1") (pinfunction "1_1") (pintype "passive"))
      (node (ref "S1") (pin "1") (pinfunction "P$1_1") (pintype "bidirectional"))
      (node (ref "S1") (pin "2") (pinfunction "P$2_2") (pintype "bidirectional"))
    )
    (net (code "102") (name "Net-(S2-P$1)") (class "Default")
      (node (ref "C5") (pin "2") (pinfunction "2_2") (pintype "passive"))
      (node (ref "RN13") (pin "7") (pinfunction "7_7") (pintype "passive"))
      (node (ref "RN7") (pin "2") (pinfunction "2_2") (pintype "passive"))
      (node (ref "S2") (pin "1") (pinfunction "P$1_1") (pintype "bidirectional"))
      (node (ref "S2") (pin "2") (pinfunction "P$2_2") (pintype "bidirectional"))
    )
    (net (code "103") (name "Net-(S3-P$1)") (class "Default")
      (node (ref "C3") (pin "1") (pinfunction "1_1") (pintype "passive"))
      (node (ref "RN13") (pin "6") (pinfunction "6_6") (pintype "passive"))
      (node (ref "RN7") (pin "3") (pinfunction "3_3") (pintype "passive"))
      (node (ref "S3") (pin "1") (pinfunction "P$1_1") (pintype "bidirectional"))
      (node (ref "S3") (pin "2") (pinfunction "P$2_2") (pintype "bidirectional"))
    )
    (net (code "104") (name "Net-(S4-P$1)") (class "Default")
      (node (ref "C2") (pin "1") (pinfunction "1_1") (pintype "passive"))
      (node (ref "RN13") (pin "5") (pinfunction "5_5") (pintype "passive"))
      (node (ref "RN7") (pin "4") (pinfunction "4_4") (pintype "passive"))
      (node (ref "S4") (pin "1") (pinfunction "P$1_1") (pintype "bidirectional"))
      (node (ref "S4") (pin "2") (pinfunction "P$2_2") (pintype "bidirectional"))
    )
    (net (code "105") (name "Net-(S5-P$1)") (class "Default")
      (node (ref "C8") (pin "1") (pinfunction "1_1") (pintype "passive"))
      (node (ref "R17") (pin "1") (pinfunction "1_1") (pintype "passive"))
      (node (ref "R18") (pin "2") (pinfunction "2_2") (pintype "passive"))
      (node (ref "S5") (pin "1") (pinfunction "P$1_1") (pintype "bidirectional"))
      (node (ref "S5") (pin "2") (pinfunction "P$2_2") (pintype "bidirectional"))
    )
    (net (code "106") (name "Net-(U$3-FB)") (class "Default")
      (node (ref "C9") (pin "2") (pinfunction "2_2") (pintype "passive"))
      (node (ref "R19") (pin "1") (pinfunction "1_1") (pintype "passive"))
      (node (ref "R20") (pin "2") (pinfunction "2_2") (pintype "passive"))
      (node (ref "U$3") (pin "5") (pinfunction "FB_5") (pintype "bidirectional"))
    )
    (net (code "107") (name "Net-(U$3-LX)") (class "Default")
      (node (ref "L2") (pin "P$2") (pinfunction "P$2_P$2") (pintype "bidirectional"))
      (node (ref "U$3") (pin "3") (pinfunction "LX_3") (pintype "bidirectional"))
    )
    (net (code "108") (name "Net-(U$7-FB)") (class "Default")
      (node (ref "C23") (pin "2") (pinfunction "2_2") (pintype "passive"))
      (node (ref "R28") (pin "1") (pinfunction "1_1") (pintype "passive"))
      (node (ref "R29") (pin "2") (pinfunction "2_2") (pintype "passive"))
      (node (ref "U$7") (pin "5") (pinfunction "FB_5") (pintype "bidirectional"))
    )
    (net (code "109") (name "Net-(U$7-LX)") (class "Default")
      (node (ref "L4") (pin "P$2") (pinfunction "P$2_P$2") (pintype "bidirectional"))
      (node (ref "U$7") (pin "3") (pinfunction "LX_3") (pintype "bidirectional"))
    )
    (net (code "110") (name "Net-(U$11-FB)") (class "Default")
      (node (ref "C49") (pin "2") (pinfunction "2_2") (pintype "passive"))
      (node (ref "R2") (pin "1") (pinfunction "1_1") (pintype "passive"))
      (node (ref "R5") (pin "2") (pinfunction "2_2") (pintype "passive"))
      (node (ref "U$11") (pin "5") (pinfunction "FB_5") (pintype "bidirectional"))
    )
    (net (code "111") (name "Net-(U$11-LX)") (class "Default")
      (node (ref "L3") (pin "P$2") (pinfunction "P$2_P$2") (pintype "bidirectional"))
      (node (ref "U$11") (pin "3") (pinfunction "LX_3") (pintype "bidirectional"))
    )
    (net (code "112") (name "Net-(U1-XA)") (class "Default")
      (node (ref "C81") (pin "2") (pinfunction "2_2") (pintype "passive"))
      (node (ref "Q2") (pin "2") (pinfunction "2_2") (pintype "passive"))
      (node (ref "U1") (pin "2") (pinfunction "XA_2") (pintype "input"))
    )
    (net (code "113") (name "Net-(U1-XB)") (class "Default")
      (node (ref "C82") (pin "2") (pinfunction "2_2") (pintype "passive"))
      (node (ref "Q2") (pin "1") (pinfunction "1_1") (pintype "passive"))
      (node (ref "U1") (pin "3") (pinfunction "XB_3") (pintype "input"))
    )
    (net (code "114") (name "Net-(U3-RA2{slash}AN2{slash}C1OUT{slash}T0CKI{slash}INT2{slash}SRQ)") (class "Default")
      (node (ref "C1") (pin "2") (pinfunction "2_2") (pintype "passive"))
      (node (ref "U3") (pin "17") (pinfunction "RA2/AN2/C1OUT/T0CKI/INT2/SRQ_17") (pintype "input"))
    )
    (net (code "115") (name "Net-(U3-RA3{slash}~{MCLR{slash}VPP})") (class "Default")
      (node (ref "R11") (pin "1") (pinfunction "1_1") (pintype "passive"))
      (node (ref "SV1") (pin "1") (pinfunction "1_1") (pintype "passive"))
      (node (ref "U3") (pin "4") (pinfunction "RA3/~{MCLR/VPP}_4") (pintype "input"))
    )
    (net (code "116") (name "Net-(U3-RA4{slash}AN3{slash}OSC2{slash}CLKOUT)") (class "Default")
      (node (ref "C4") (pin "2") (pinfunction "2_2") (pintype "passive"))
      (node (ref "Q1") (pin "2") (pinfunction "2_2") (pintype "passive"))
      (node (ref "U3") (pin "3") (pinfunction "RA4/AN3/OSC2/CLKOUT_3") (pintype "bidirectional"))
    )
    (net (code "117") (name "Net-(U3-RA5{slash}OSC1{slash}CLKIN{slash}T13CKI)") (class "Default")
      (node (ref "C6") (pin "2") (pinfunction "2_2") (pintype "passive"))
      (node (ref "Q1") (pin "1") (pinfunction "1_1") (pintype "passive"))
      (node (ref "U3") (pin "2") (pinfunction "RA5/OSC1/CLKIN/T13CKI_2") (pintype "bidirectional"))
    )
    (net (code "118") (name "Net-(U3-RB4{slash}AN10{slash}SDI{slash}SDA)") (class "Default")
      (node (ref "R12") (pin "1") (pinfunction "1_1") (pintype "passive"))
      (node (ref "U3") (pin "13") (pinfunction "RB4/AN10/SDI/SDA_13") (pintype "bidirectional"))
    )
    (net (code "119") (name "Net-(U3-RB6{slash}SCK{slash}SCL)") (class "Default")
      (node (ref "R1") (pin "1") (pinfunction "1_1") (pintype "passive"))
      (node (ref "U3") (pin "11") (pinfunction "RB6/SCK/SCL_11") (pintype "bidirectional"))
      (node (ref "U3") (pin "16") (pinfunction "RC0/AN4/C2IN+_16") (pintype "bidirectional"))
    )
    (net (code "120") (name "Net-(U3-RB7{slash}TX{slash}CK)") (class "Default")
      (node (ref "R8") (pin "2") (pinfunction "2_2") (pintype "passive"))
      (node (ref "U3") (pin "10") (pinfunction "RB7/TX/CK_10") (pintype "bidirectional"))
    )
    (net (code "121") (name "Net-(U3-RC1{slash}AN5{slash}C12IN1-)") (class "Default")
      (node (ref "R4") (pin "1") (pinfunction "1_1") (pintype "passive"))
      (node (ref "U3") (pin "15") (pinfunction "RC1/AN5/C12IN1-_15") (pintype "bidirectional"))
    )
    (net (code "122") (name "Net-(U3-RC4{slash}C2OUT{slash}P1B{slash}SRNQ)") (class "Default")
      (node (ref "R3") (pin "1") (pinfunction "1_1") (pintype "passive"))
      (node (ref "U3") (pin "6") (pinfunction "RC4/C2OUT/P1B/SRNQ_6") (pintype "bidirectional"))
      (node (ref "U3") (pin "9") (pinfunction "RC7/AN9/SDO_9") (pintype "bidirectional"))
    )
    (net (code "123") (name "Net-(U4-HOLD#)") (class "Default")
      (node (ref "SJ2") (pin "2") (pinfunction "2_2") (pintype "passive"))
      (node (ref "U4") (pin "7") (pinfunction "HOLD#_7") (pintype "bidirectional"))
    )
    (net (code "124") (name "Net-(U4-SO)") (class "Default")
      (node (ref "R37") (pin "1") (pinfunction "1_1") (pintype "passive"))
      (node (ref "U4") (pin "2") (pinfunction "SO_2") (pintype "bidirectional"))
    )
    (net (code "125") (name "PLL_CLK0") (class "Default")
      (node (ref "IC1") (pin "22") (pinfunction "CLK0_22") (pintype "input"))
      (node (ref "U1") (pin "10") (pinfunction "CLK0_10") (pintype "output"))
    )
    (net (code "126") (name "PLL_CLK1") (class "Default")
      (node (ref "IC1") (pin "23") (pinfunction "CLK1_23") (pintype "input"))
      (node (ref "U1") (pin "9") (pinfunction "CLK1_9") (pintype "output"))
    )
    (net (code "127") (name "PLL_CLK2") (class "Default")
      (node (ref "IC1") (pin "24") (pinfunction "CLK2_24") (pintype "input"))
      (node (ref "U1") (pin "6") (pinfunction "CLK2_6") (pintype "output"))
    )
    (net (code "128") (name "RESET") (class "Default")
      (node (ref "IC1") (pin "28") (pinfunction "IO_8_28") (pintype "bidirectional"))
      (node (ref "R17") (pin "2") (pinfunction "2_2") (pintype "passive"))
    )
    (net (code "129") (name "RGB_B") (class "Default")
      (node (ref "IC1") (pin "7") (pinfunction "IO_2_7") (pintype "bidirectional"))
      (node (ref "RN1") (pin "8") (pinfunction "8_8") (pintype "passive"))
    )
    (net (code "130") (name "RGB_G") (class "Default")
      (node (ref "IC1") (pin "11") (pinfunction "IO_5_11") (pintype "bidirectional"))
      (node (ref "RN1") (pin "6") (pinfunction "6_6") (pintype "passive"))
    )
    (net (code "131") (name "RGB_R") (class "Default")
      (node (ref "IC1") (pin "10") (pinfunction "IO_4_10") (pintype "bidirectional"))
      (node (ref "RN1") (pin "7") (pinfunction "7_7") (pintype "passive"))
    )
    (net (code "132") (name "RS485_DIR") (class "Default")
      (node (ref "IC1") (pin "33") (pinfunction "IO_11_33") (pintype "bidirectional"))
      (node (ref "IC2") (pin "2") (pinfunction "~{RE}_2") (pintype "input"))
      (node (ref "IC2") (pin "3") (pinfunction "DE_3") (pintype "input"))
      (node (ref "R24") (pin "2") (pinfunction "2_2") (pintype "passive"))
    )
    (net (code "133") (name "RS485_RX") (class "Default")
      (node (ref "IC1") (pin "31") (pinfunction "IO_9_31") (pintype "bidirectional"))
      (node (ref "IC2") (pin "1") (pinfunction "R_1") (pintype "input"))
      (node (ref "R25") (pin "2") (pinfunction "2_2") (pintype "passive"))
    )
    (net (code "134") (name "RS485_TX") (class "Default")
      (node (ref "IC1") (pin "32") (pinfunction "IO_10_32") (pintype "bidirectional"))
      (node (ref "IC2") (pin "4") (pinfunction "D_4") (pintype "input"))
    )
    (net (code "135") (name "SWS_0") (class "Default")
      (node (ref "IC1") (pin "55") (pinfunction "CLK12_55") (pintype "input"))
      (node (ref "RN7") (pin "5") (pinfunction "5_5") (pintype "passive"))
    )
    (net (code "136") (name "SWS_1") (class "Default")
      (node (ref "IC1") (pin "54") (pinfunction "CLK13_54") (pintype "input"))
      (node (ref "RN7") (pin "6") (pinfunction "6_6") (pintype "passive"))
    )
    (net (code "137") (name "SWS_2") (class "Default")
      (node (ref "IC1") (pin "53") (pinfunction "CLK14_53") (pintype "input"))
      (node (ref "RN7") (pin "7") (pinfunction "7_7") (pintype "passive"))
    )
    (net (code "138") (name "SWS_3") (class "Default")
      (node (ref "IC1") (pin "52") (pinfunction "CLK15_52") (pintype "input"))
      (node (ref "RN7") (pin "8") (pinfunction "8_8") (pintype "passive"))
    )
    (net (code "139") (name "SW_0") (class "Default")
      (node (ref "IC1") (pin "61") (pinfunction "IO_23_61") (pintype "bidirectional"))
      (node (ref "RN3") (pin "5") (pinfunction "5_5") (pintype "passive"))
    )
    (net (code "140") (name "SW_1") (class "Default")
      (node (ref "IC1") (pin "60") (pinfunction "IO_22_60") (pintype "bidirectional"))
      (node (ref "RN3") (pin "6") (pinfunction "6_6") (pintype "passive"))
    )
    (net (code "141") (name "SW_2") (class "Default")
      (node (ref "IC1") (pin "59") (pinfunction "IO_21_59") (pintype "bidirectional"))
      (node (ref "RN3") (pin "7") (pinfunction "7_7") (pintype "passive"))
    )
    (net (code "142") (name "SW_3") (class "Default")
      (node (ref "IC1") (pin "58") (pinfunction "IO_20_58") (pintype "bidirectional"))
      (node (ref "RN3") (pin "8") (pinfunction "8_8") (pintype "passive"))
    )
    (net (code "143") (name "TCK") (class "Default")
      (node (ref "IC1") (pin "16") (pinfunction "TCK_16") (pintype "input"))
      (node (ref "R1") (pin "2") (pinfunction "2_2") (pintype "passive"))
    )
    (net (code "144") (name "TDI") (class "Default")
      (node (ref "IC1") (pin "15") (pinfunction "TDI_15") (pintype "input"))
      (node (ref "R3") (pin "2") (pinfunction "2_2") (pintype "passive"))
    )
    (net (code "145") (name "TDO") (class "Default")
      (node (ref "IC1") (pin "20") (pinfunction "TDO_20") (pintype "output"))
      (node (ref "R12") (pin "2") (pinfunction "2_2") (pintype "passive"))
    )
    (net (code "146") (name "TMS") (class "Default")
      (node (ref "IC1") (pin "18") (pinfunction "TMS_18") (pintype "input"))
      (node (ref "R4") (pin "2") (pinfunction "2_2") (pintype "passive"))
    )
    (net (code "147") (name "USB_D+") (class "Default")
      (node (ref "D3") (pin "3") (pinfunction "D+_I_3") (pintype "bidirectional"))
      (node (ref "IC1") (pin "86") (pinfunction "IO_36_86") (pintype "bidirectional"))
    )
    (net (code "148") (name "USB_D-") (class "Default")
      (node (ref "D3") (pin "4") (pinfunction "D-_I_4") (pintype "bidirectional"))
      (node (ref "IC1") (pin "85") (pinfunction "IO_35_85") (pintype "bidirectional"))
    )
    (net (code "149") (name "USB_ID") (class "Default")
      (node (ref "IC1") (pin "87") (pinfunction "IO_37_87") (pintype "bidirectional"))
      (node (ref "R35") (pin "1") (pinfunction "1_1") (pintype "passive"))
      (node (ref "R6") (pin "2") (pinfunction "2_2") (pintype "passive"))
    )
    (net (code "150") (name "VCCA") (class "Default")
      (node (ref "B3") (pin "2") (pinfunction "P$2_2") (pintype "bidirectional"))
      (node (ref "C58") (pin "1") (pinfunction "1_1") (pintype "passive"))
      (node (ref "C59") (pin "1") (pinfunction "1_1") (pintype "passive"))
      (node (ref "IC1") (pin "107") (pinfunction "VCCA2_107") (pintype "power_in"))
      (node (ref "IC1") (pin "3") (pinfunction "VCCA3_3") (pintype "power_in"))
      (node (ref "IC1") (pin "35") (pinfunction "VCCA1_35") (pintype "power_in"))
      (node (ref "IC1") (pin "75") (pinfunction "VCCA4_75") (pintype "power_in"))
      (node (ref "IC1") (pin "94") (pinfunction "MSEL0_94") (pintype "input"))
      (node (ref "IC1") (pin "97") (pinfunction "MSEL2_97") (pintype "input"))
    )
    (net (code "151") (name "VCCD") (class "Default")
      (node (ref "B4") (pin "2") (pinfunction "P$2_2") (pintype "bidirectional"))
      (node (ref "C61") (pin "1") (pinfunction "1_1") (pintype "passive"))
      (node (ref "C64") (pin "1") (pinfunction "1_1") (pintype "passive"))
      (node (ref "IC1") (pin "1") (pinfunction "VCCD_PLL3_1") (pintype "power_in"))
      (node (ref "IC1") (pin "37") (pinfunction "VCCD_PLL1_37") (pintype "power_in"))
      (node (ref "IC1") (pin "73") (pinfunction "VCCD_PLL4_73") (pintype "power_in"))
    )
    (net (code "152") (name "VCCINT") (class "Default")
      (node (ref "B2") (pin "2") (pinfunction "P$2_2") (pintype "bidirectional"))
      (node (ref "C44") (pin "1") (pinfunction "1_1") (pintype "passive"))
      (node (ref "C45") (pin "1") (pinfunction "1_1") (pintype "passive"))
      (node (ref "C46") (pin "1") (pinfunction "1_1") (pintype "passive"))
      (node (ref "C47") (pin "1") (pinfunction "1_1") (pintype "passive"))
      (node (ref "IC1") (pin "102") (pinfunction "VCCINT_9_102") (pintype "power_in"))
      (node (ref "IC1") (pin "116") (pinfunction "VCCINT_10_116") (pintype "power_in"))
      (node (ref "IC1") (pin "124") (pinfunction "VCCINT_11_124") (pintype "power_in"))
      (node (ref "IC1") (pin "138") (pinfunction "VCCINT_12_138") (pintype "power_in"))
      (node (ref "IC1") (pin "29") (pinfunction "VCCINT_2_29") (pintype "power_in"))
      (node (ref "IC1") (pin "34") (pinfunction "VCCINT_3_34") (pintype "power_in"))
      (node (ref "IC1") (pin "38") (pinfunction "VCCINT_4_38") (pintype "power_in"))
      (node (ref "IC1") (pin "45") (pinfunction "VCCINT_5_45") (pintype "power_in"))
      (node (ref "IC1") (pin "5") (pinfunction "VCCINT_1_5") (pintype "power_in"))
      (node (ref "IC1") (pin "70") (pinfunction "VCCINT_6_70") (pintype "power_in"))
      (node (ref "IC1") (pin "78") (pinfunction "VCCINT_7_78") (pintype "power_in"))
      (node (ref "IC1") (pin "84") (pinfunction "VCCINT_8_84") (pintype "power_in"))
    )
    (net (code "153") (name "VCCIO") (class "Default")
      (node (ref "B1") (pin "2") (pinfunction "P$2_2") (pintype "bidirectional"))
      (node (ref "C32") (pin "1") (pinfunction "1_1") (pintype "passive"))
      (node (ref "C34") (pin "1") (pinfunction "1_1") (pintype "passive"))
      (node (ref "C35") (pin "1") (pinfunction "1_1") (pintype "passive"))
      (node (ref "C36") (pin "1") (pinfunction "1_1") (pintype "passive"))
      (node (ref "C37") (pin "1") (pinfunction "1_1") (pintype "passive"))
      (node (ref "C38") (pin "1") (pinfunction "1_1") (pintype "passive"))
      (node (ref "C39") (pin "1") (pinfunction "1_1") (pintype "passive"))
      (node (ref "C40") (pin "1") (pinfunction "1_1") (pintype "passive"))
      (node (ref "IC1") (pin "117") (pinfunction "VCCIO7_1_117") (pintype "power_in"))
      (node (ref "IC1") (pin "122") (pinfunction "VCCIO7_2_122") (pintype "power_in"))
      (node (ref "IC1") (pin "130") (pinfunction "VCCIO8_1_130") (pintype "power_in"))
      (node (ref "IC1") (pin "139") (pinfunction "VCCIO8_2_139") (pintype "power_in"))
      (node (ref "IC1") (pin "17") (pinfunction "VCCIO1_17") (pintype "power_in"))
      (node (ref "IC1") (pin "26") (pinfunction "VCCIO2_26") (pintype "power_in"))
      (node (ref "IC1") (pin "40") (pinfunction "VCCIO3_1_40") (pintype "power_in"))
      (node (ref "IC1") (pin "47") (pinfunction "VCCIO3_2_47") (pintype "power_in"))
      (node (ref "IC1") (pin "56") (pinfunction "VCCIO4_1_56") (pintype "power_in"))
      (node (ref "IC1") (pin "62") (pinfunction "VCCIO4_2_62") (pintype "power_in"))
      (node (ref "IC1") (pin "81") (pinfunction "VCCIO5_81") (pintype "power_in"))
      (node (ref "IC1") (pin "93") (pinfunction "VCCIO6_93") (pintype "power_in"))
      (node (ref "R33") (pin "1") (pinfunction "1_1") (pintype "passive"))
      (node (ref "R34") (pin "1") (pinfunction "1_1") (pintype "passive"))
      (node (ref "R36") (pin "2") (pinfunction "2_2") (pintype "passive"))
    )
    (net (code "154") (name "VIN") (class "Default")
      (node (ref "C12") (pin "1") (pinfunction "1_1") (pintype "passive"))
      (node (ref "C13") (pin "1") (pinfunction "1_1") (pintype "passive"))
      (node (ref "D1") (pin "K") (pinfunction "C_K") (pintype "passive"))
      (node (ref "D2") (pin "5") (pinfunction "VCC_5") (pintype "bidirectional"))
      (node (ref "JP1") (pin "2") (pinfunction "2_2") (pintype "passive"))
      (node (ref "Q3") (pin "3") (pinfunction "D_3") (pintype "passive"))
      (node (ref "X1") (pin "1") (pinfunction "1_1") (pintype "passive"))
    )
    (net (code "155") (name "unconnected-(RN1-Pad4)") (class "Default")
      (node (ref "RN1") (pin "4") (pinfunction "4_4") (pintype "passive"))
    )
    (net (code "156") (name "unconnected-(RN1-Pad5)") (class "Default")
      (node (ref "RN1") (pin "5") (pinfunction "5_5") (pintype "passive"))
    )
    (net (code "157") (name "unconnected-(U$1-HOTPLUG-PadP$19)") (class "Default")
      (node (ref "U$1") (pin "P$19") (pinfunction "HOTPLUG_P$19") (pintype "bidirectional"))
    )
    (net (code "158") (name "unconnected-(U$1-SCL-PadP$15)") (class "Default")
      (node (ref "U$1") (pin "P$15") (pinfunction "SCL_P$15") (pintype "bidirectional"))
    )
    (net (code "159") (name "unconnected-(U$1-SDA-PadP$16)") (class "Default")
      (node (ref "U$1") (pin "P$16") (pinfunction "SDA_P$16") (pintype "bidirectional"))
    )
    (net (code "160") (name "unconnected-(U$1-UTIL-PadP$14)") (class "Default")
      (node (ref "U$1") (pin "P$14") (pinfunction "UTIL_P$14") (pintype "bidirectional"))
    )
    (net (code "161") (name "unconnected-(U$1-VCC-PadP$18)") (class "Default")
      (node (ref "U$1") (pin "P$18") (pinfunction "VCC_P$18") (pintype "bidirectional"))
    )
    (net (code "162") (name "unconnected-(U3-RB5{slash}AN11{slash}RX{slash}DT-Pad12)") (class "Default")
      (node (ref "U3") (pin "12") (pinfunction "RB5/AN11/RX/DT_12") (pintype "bidirectional"))
    )
    (net (code "163") (name "unconnected-(U3-RC2{slash}AN6{slash}C12IN2-{slash}P1D-Pad14)") (class "Default")
      (node (ref "U3") (pin "14") (pinfunction "RC2/AN6/C12IN2-/P1D_14") (pintype "bidirectional"))
    )
    (net (code "164") (name "unconnected-(U3-RC3{slash}AN7{slash}C12IN3-{slash}P1C{slash}PGM-Pad7)") (class "Default")
      (node (ref "U3") (pin "7") (pinfunction "RC3/AN7/C12IN3-/P1C/PGM_7") (pintype "bidirectional"))
    )
    (net (code "165") (name "unconnected-(U3-RC5{slash}CCP1{slash}P1A-Pad5)") (class "Default")
      (node (ref "U3") (pin "5") (pinfunction "RC5/CCP1/P1A_5") (pintype "bidirectional"))
    )
    (net (code "166") (name "unconnected-(U3-RC6{slash}AN8{slash}~{SS}-Pad8)") (class "Default")
      (node (ref "U3") (pin "8") (pinfunction "RC6/AN8/~{SS}_8") (pintype "bidirectional"))
    )
    (net (code "167") (name "unconnected-(X1-Pad4)") (class "Default")
      (node (ref "X1") (pin "4") (pinfunction "4_4") (pintype "passive"))
    )
  )
)
